# Laser_Teensy_proto_edits_11-21.net
KiCad netlist of a schematic drawn in EAGLE
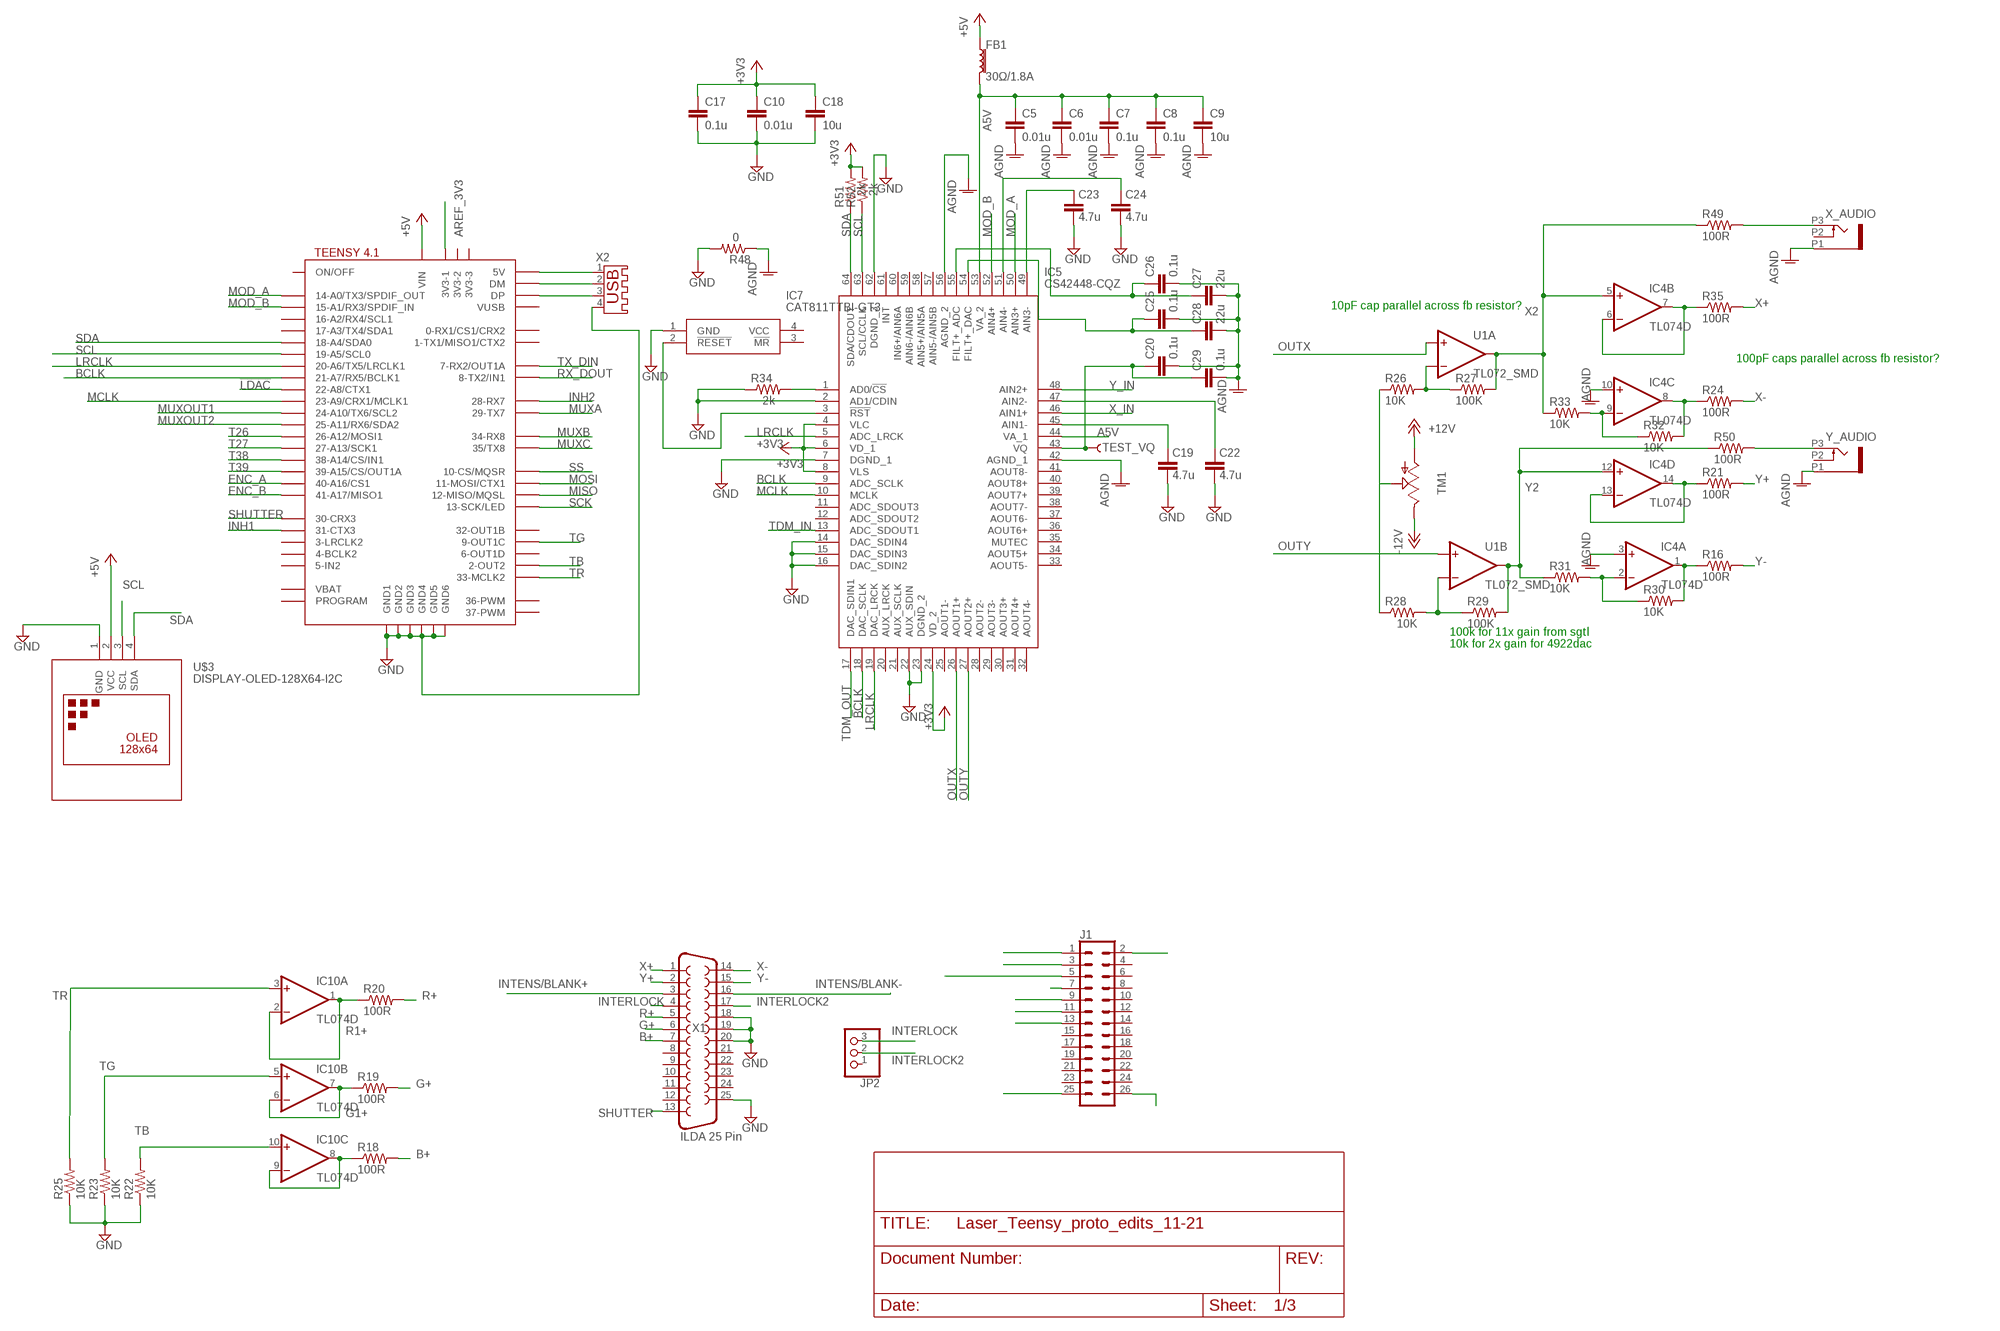
[diagram p0: schematic, sheet 1]
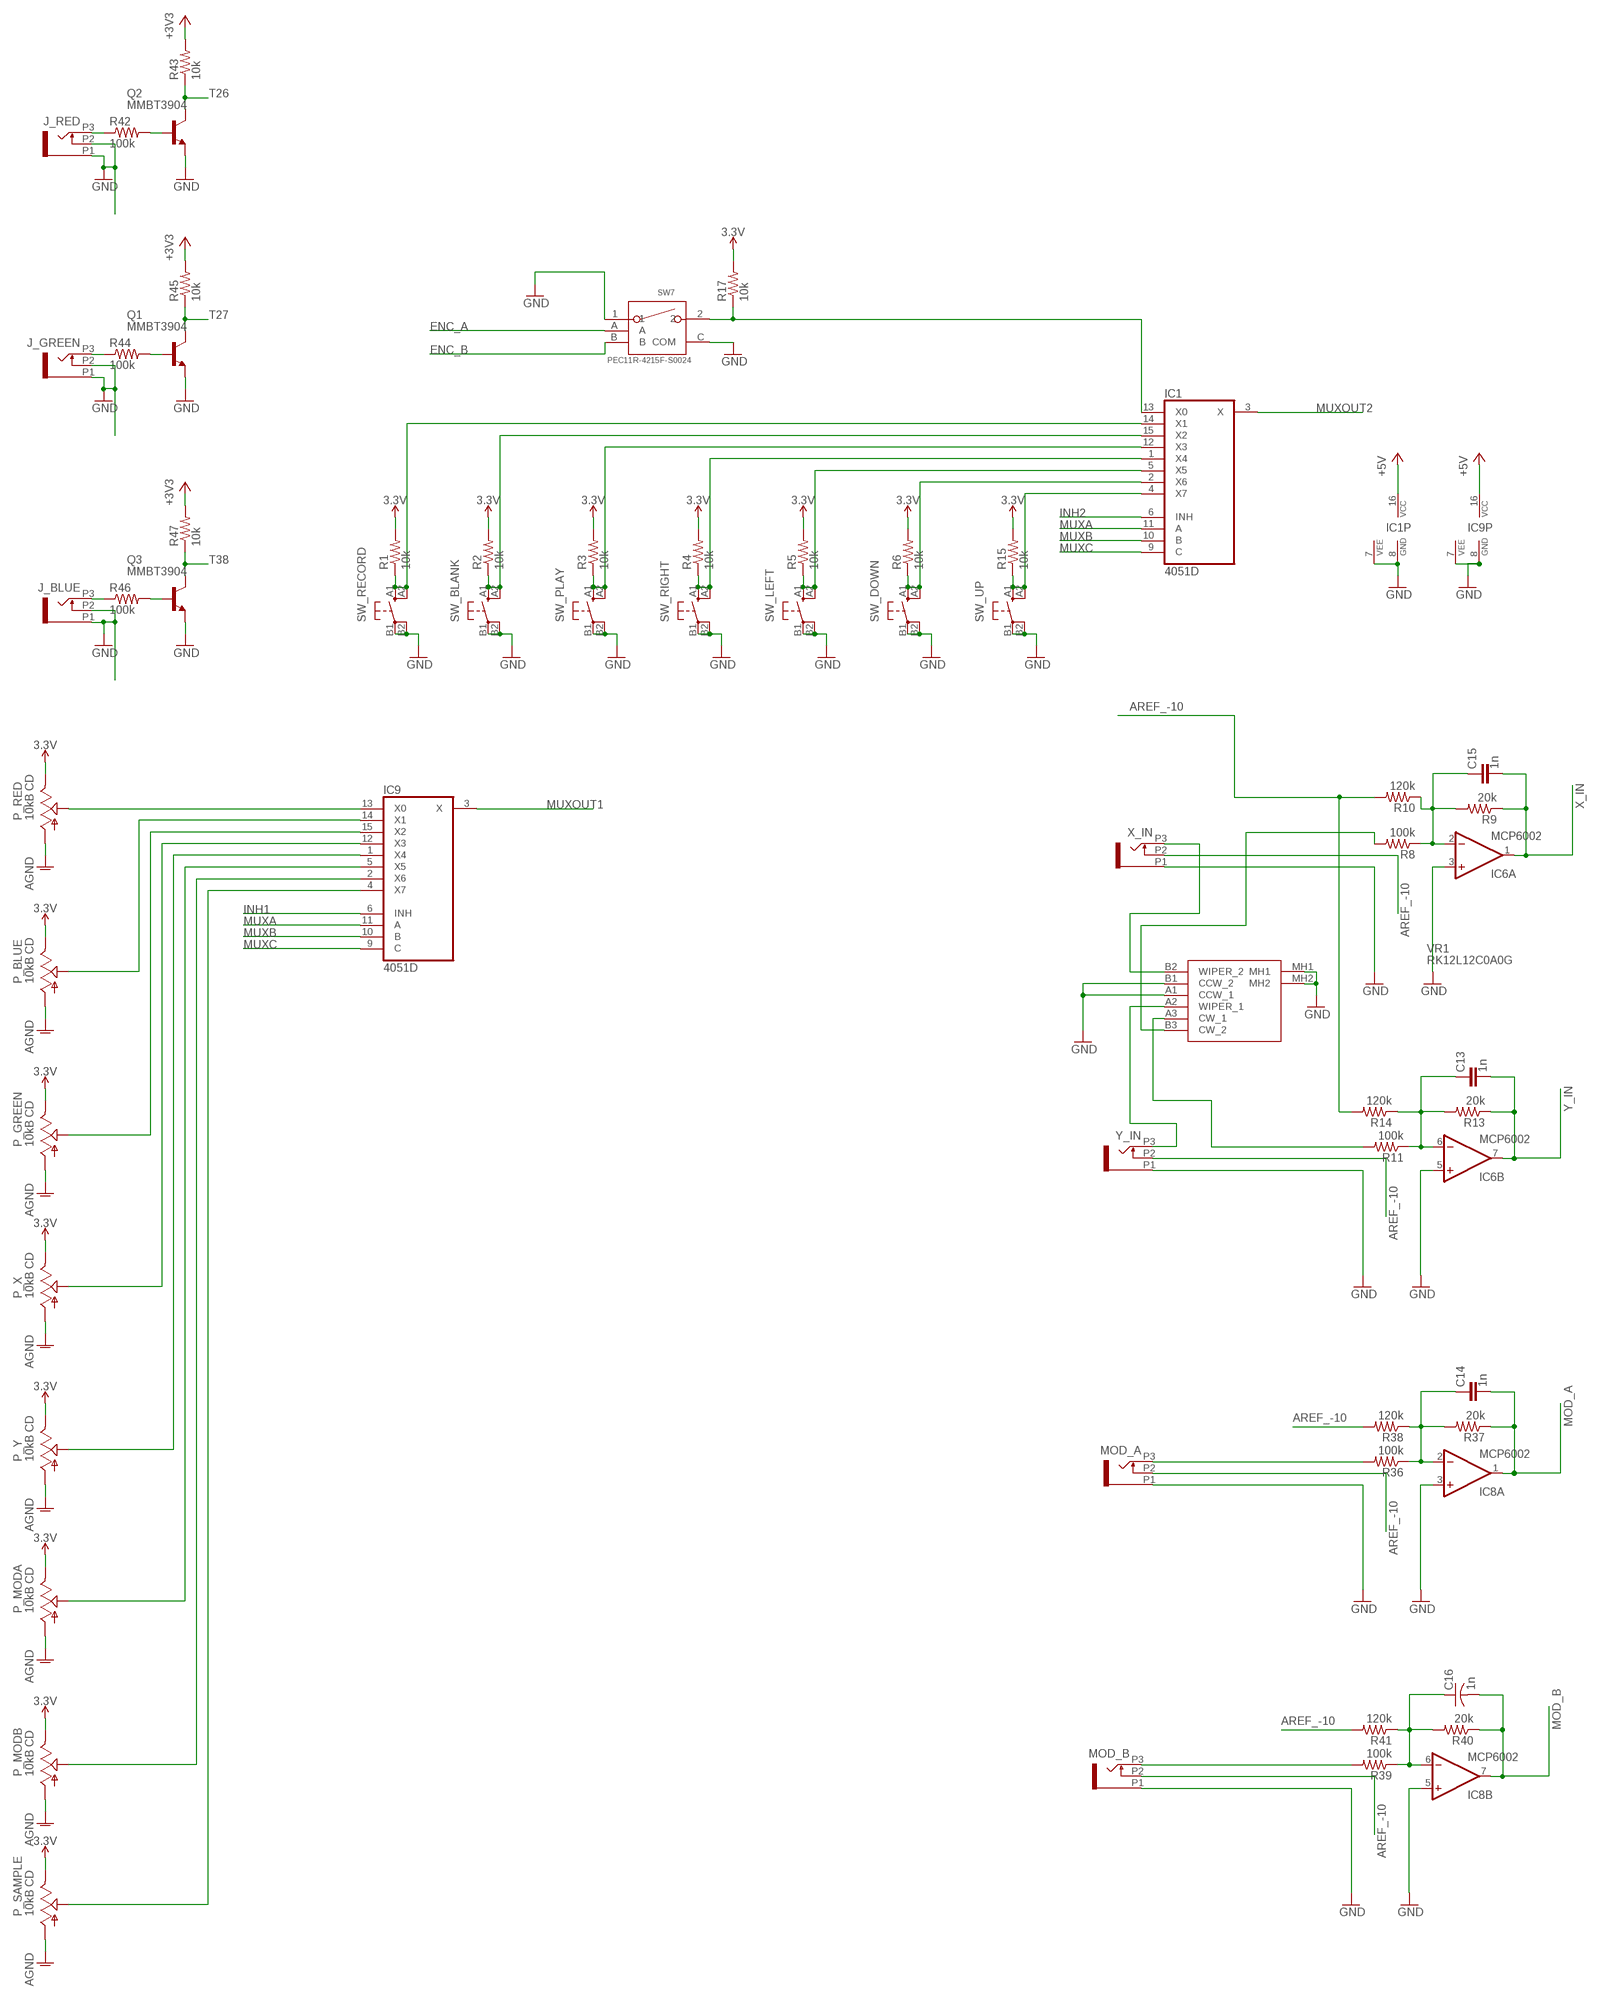
[diagram p1: schematic, sheet 2]
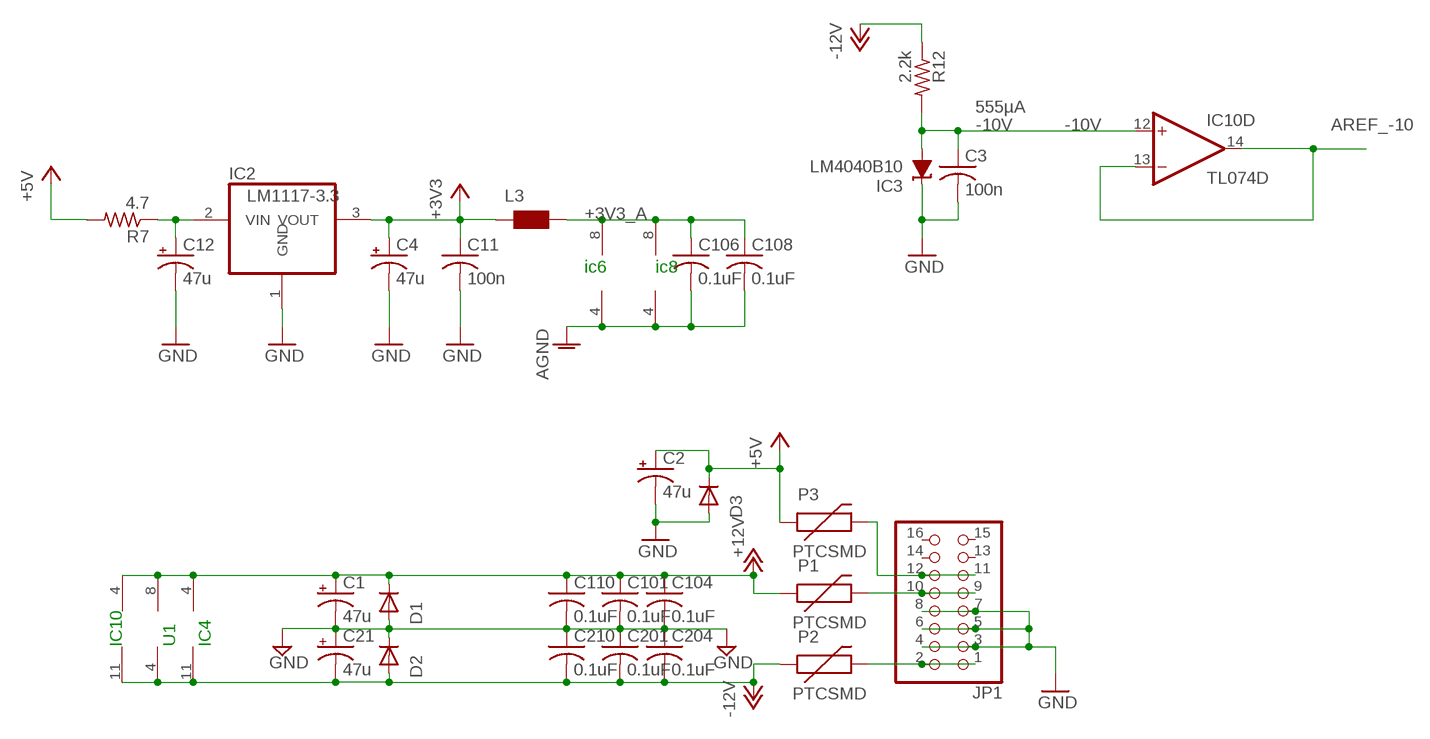
[diagram p2: schematic, sheet 3]

(export (version "E")
  (design (tool "Eeschema 10.0.6"))
  (components
    (comp (ref "C13")
      (value "1n")
      (footprint "eagle-import:C0603")
      (libsource (lib "eagle-import") (part "C-EUC0603"))
    )
    (comp (ref "C14")
      (value "1n")
      (footprint "eagle-import:C0603")
      (libsource (lib "eagle-import") (part "C-EUC0603"))
    )
    (comp (ref "C15")
      (value "1n")
      (footprint "eagle-import:C0603")
      (libsource (lib "eagle-import") (part "C-EUC0603"))
    )
    (comp (ref "C16")
      (value "1n")
      (footprint "eagle-import:C0603K")
      (libsource (lib "eagle-import") (part "rcl_334_C-USC0603K"))
    )
    (comp (ref "IC1")
      (value "4051D")
      (footprint "eagle-import:SO16")
      (libsource (lib "eagle-import") (part "4051D"))
    )
    (comp (ref "IC6")
      (value "MCP6002")
      (footprint "eagle-import:SO08")
      (libsource (lib "eagle-import") (part "TL072D"))
    )
    (comp (ref "IC8")
      (value "MCP6002")
      (footprint "eagle-import:SO08")
      (libsource (lib "eagle-import") (part "TL072D"))
    )
    (comp (ref "IC9")
      (value "4051D")
      (footprint "eagle-import:SO16")
      (libsource (lib "eagle-import") (part "4051D"))
    )
    (comp (ref "J_BLUE")
      (value "PJ301_THONKICONN6")
      (footprint "eagle-import:WQP_PJ_301M6")
      (libsource (lib "eagle-import") (part "PJ301_THONKICONN6"))
    )
    (comp (ref "J_GREEN")
      (value "PJ301_THONKICONN6")
      (footprint "eagle-import:WQP_PJ_301M6")
      (libsource (lib "eagle-import") (part "PJ301_THONKICONN6"))
    )
    (comp (ref "J_RED")
      (value "PJ301_THONKICONN6")
      (footprint "eagle-import:WQP_PJ_301M6")
      (libsource (lib "eagle-import") (part "PJ301_THONKICONN6"))
    )
    (comp (ref "MOD_A")
      (value "PJ301_THONKICONN6")
      (footprint "eagle-import:WQP_PJ_301M6")
      (libsource (lib "eagle-import") (part "og-pj301_variations_PJ301_THONKICONN6"))
    )
    (comp (ref "MOD_B")
      (value "PJ301_THONKICONN6")
      (footprint "eagle-import:WQP_PJ_301M6")
      (libsource (lib "eagle-import") (part "og-pj301_variations_PJ301_THONKICONN6"))
    )
    (comp (ref "P_BLUE")
      (value "10kB CD")
      (footprint "eagle-import:ALPS_POT_VERTICAL_PS")
      (libsource (lib "eagle-import") (part "POT_USVERTICAL_PS"))
    )
    (comp (ref "P_GREEN")
      (value "10kB CD")
      (footprint "eagle-import:ALPS_POT_VERTICAL_PS")
      (libsource (lib "eagle-import") (part "POT_USVERTICAL_PS"))
    )
    (comp (ref "P_MODA")
      (value "10kB CD")
      (footprint "eagle-import:ALPS_POT_VERTICAL_PS")
      (libsource (lib "eagle-import") (part "POT_USVERTICAL_PS"))
    )
    (comp (ref "P_MODB")
      (value "10kB CD")
      (footprint "eagle-import:ALPS_POT_VERTICAL_PS")
      (libsource (lib "eagle-import") (part "POT_USVERTICAL_PS"))
    )
    (comp (ref "P_RED")
      (value "10kB CD")
      (footprint "eagle-import:ALPS_POT_VERTICAL_PS")
      (libsource (lib "eagle-import") (part "POT_USVERTICAL_PS"))
    )
    (comp (ref "P_SAMPLE")
      (value "10kB CD")
      (footprint "eagle-import:ALPS_POT_VERTICAL_PS")
      (libsource (lib "eagle-import") (part "POT_USVERTICAL_PS"))
    )
    (comp (ref "P_X")
      (value "10kB CD")
      (footprint "eagle-import:ALPS_POT_VERTICAL_PS")
      (libsource (lib "eagle-import") (part "POT_USVERTICAL_PS"))
    )
    (comp (ref "P_Y")
      (value "10kB CD")
      (footprint "eagle-import:ALPS_POT_VERTICAL_PS")
      (libsource (lib "eagle-import") (part "POT_USVERTICAL_PS"))
    )
    (comp (ref "Q1")
      (value "MMBT3904")
      (footprint "eagle-import:SOT23-BEC")
      (libsource (lib "eagle-import") (part "-NPN-SOT23-BECMMBT3904LT1"))
    )
    (comp (ref "Q2")
      (value "MMBT3904")
      (footprint "eagle-import:SOT23-BEC")
      (libsource (lib "eagle-import") (part "-NPN-SOT23-BECMMBT3904LT1"))
    )
    (comp (ref "Q3")
      (value "MMBT3904")
      (footprint "eagle-import:SOT23-BEC")
      (libsource (lib "eagle-import") (part "-NPN-SOT23-BECMMBT3904LT1"))
    )
    (comp (ref "R1")
      (value "10k")
      (footprint "eagle-import:R0603")
      (libsource (lib "eagle-import") (part "rcl_334_R-US_R0603"))
    )
    (comp (ref "R2")
      (value "10k")
      (footprint "eagle-import:R0603")
      (libsource (lib "eagle-import") (part "rcl_334_R-US_R0603"))
    )
    (comp (ref "R3")
      (value "10k")
      (footprint "eagle-import:R0603")
      (libsource (lib "eagle-import") (part "rcl_334_R-US_R0603"))
    )
    (comp (ref "R4")
      (value "10k")
      (footprint "eagle-import:R0603")
      (libsource (lib "eagle-import") (part "rcl_334_R-US_R0603"))
    )
    (comp (ref "R5")
      (value "10k")
      (footprint "eagle-import:R0603")
      (libsource (lib "eagle-import") (part "rcl_334_R-US_R0603"))
    )
    (comp (ref "R6")
      (value "10k")
      (footprint "eagle-import:R0603")
      (libsource (lib "eagle-import") (part "rcl_334_R-US_R0603"))
    )
    (comp (ref "R8")
      (value "100k")
      (footprint "eagle-import:R0603")
      (libsource (lib "eagle-import") (part "rcl_334_R-US_R0603"))
    )
    (comp (ref "R9")
      (value "20k")
      (footprint "eagle-import:R0603")
      (libsource (lib "eagle-import") (part "rcl_334_R-US_R0603"))
    )
    (comp (ref "R10")
      (value "120k")
      (footprint "eagle-import:R0603")
      (libsource (lib "eagle-import") (part "rcl_334_R-US_R0603"))
    )
    (comp (ref "R11")
      (value "100k")
      (footprint "eagle-import:R0603")
      (libsource (lib "eagle-import") (part "rcl_334_R-US_R0603"))
    )
    (comp (ref "R13")
      (value "20k")
      (footprint "eagle-import:R0603")
      (libsource (lib "eagle-import") (part "rcl_334_R-US_R0603"))
    )
    (comp (ref "R14")
      (value "120k")
      (footprint "eagle-import:R0603")
      (libsource (lib "eagle-import") (part "rcl_334_R-US_R0603"))
    )
    (comp (ref "R15")
      (value "10k")
      (footprint "eagle-import:R0603")
      (libsource (lib "eagle-import") (part "rcl_334_R-US_R0603"))
    )
    (comp (ref "R17")
      (value "10k")
      (footprint "eagle-import:R0603")
      (libsource (lib "eagle-import") (part "rcl_334_R-US_R0603"))
    )
    (comp (ref "R36")
      (value "100k")
      (footprint "eagle-import:R0603")
      (libsource (lib "eagle-import") (part "rcl_334_R-US_R0603"))
    )
    (comp (ref "R37")
      (value "20k")
      (footprint "eagle-import:R0603")
      (libsource (lib "eagle-import") (part "rcl_334_R-US_R0603"))
    )
    (comp (ref "R38")
      (value "120k")
      (footprint "eagle-import:R0603")
      (libsource (lib "eagle-import") (part "rcl_334_R-US_R0603"))
    )
    (comp (ref "R39")
      (value "100k")
      (footprint "eagle-import:R0603")
      (libsource (lib "eagle-import") (part "rcl_334_R-US_R0603"))
    )
    (comp (ref "R40")
      (value "20k")
      (footprint "eagle-import:R0603")
      (libsource (lib "eagle-import") (part "rcl_334_R-US_R0603"))
    )
    (comp (ref "R41")
      (value "120k")
      (footprint "eagle-import:R0603")
      (libsource (lib "eagle-import") (part "rcl_334_R-US_R0603"))
    )
    (comp (ref "R42")
      (value "100k")
      (footprint "eagle-import:R0603")
      (libsource (lib "eagle-import") (part "rcl_334_R-US_R0603"))
    )
    (comp (ref "R43")
      (value "10k")
      (footprint "eagle-import:R0603")
      (libsource (lib "eagle-import") (part "rcl_334_R-US_R0603"))
    )
    (comp (ref "R44")
      (value "100k")
      (footprint "eagle-import:R0603")
      (libsource (lib "eagle-import") (part "rcl_334_R-US_R0603"))
    )
    (comp (ref "R45")
      (value "10k")
      (footprint "eagle-import:R0603")
      (libsource (lib "eagle-import") (part "rcl_334_R-US_R0603"))
    )
    (comp (ref "R46")
      (value "100k")
      (footprint "eagle-import:R0603")
      (libsource (lib "eagle-import") (part "rcl_334_R-US_R0603"))
    )
    (comp (ref "R47")
      (value "10k")
      (footprint "eagle-import:R0603")
      (libsource (lib "eagle-import") (part "rcl_334_R-US_R0603"))
    )
    (comp (ref "SW7")
      (value "PEC11R-4215F-S0024")
      (footprint "eagle-import:PEC11R-4215F-S0024")
      (fields
        (field (name "DIGIKEY_PART_NUMBER") "PEC11R-4215F-S0024-ND")
        (field (name "MANUFACTURER") "Bourns Inc.")
        (field (name "CREATED_BY") "PCBLayout.com")
      )
      (libsource (lib "eagle-import") (part "PEC11R-4215F-S0024"))
    )
    (comp (ref "SW_BLANK")
      (value "D6R")
      (footprint "eagle-import:D6R")
      (libsource (lib "eagle-import") (part "D6R"))
    )
    (comp (ref "SW_DOWN")
      (value "D6R")
      (footprint "eagle-import:D6R")
      (libsource (lib "eagle-import") (part "D6R"))
    )
    (comp (ref "SW_LEFT")
      (value "D6R")
      (footprint "eagle-import:D6R")
      (libsource (lib "eagle-import") (part "D6R"))
    )
    (comp (ref "SW_PLAY")
      (value "D6R")
      (footprint "eagle-import:D6R")
      (libsource (lib "eagle-import") (part "D6R"))
    )
    (comp (ref "SW_RECORD")
      (value "D6R")
      (footprint "eagle-import:D6R")
      (libsource (lib "eagle-import") (part "D6R"))
    )
    (comp (ref "SW_RIGHT")
      (value "D6R")
      (footprint "eagle-import:D6R")
      (libsource (lib "eagle-import") (part "D6R"))
    )
    (comp (ref "SW_UP")
      (value "D6R")
      (footprint "eagle-import:D6R")
      (libsource (lib "eagle-import") (part "D6R"))
    )
    (comp (ref "VR1")
      (value "RK12L12C0A0G")
      (footprint "eagle-import:RK12L12C0A0G")
      (fields (field (name "MOUSER_PART_NUMBER") "688-RK12L12C0A0G"))
      (libsource (lib "eagle-import") (part "RK12L12C0A0G"))
    )
    (comp (ref "X_IN")
      (value "PJ301_THONKICONN6")
      (footprint "eagle-import:WQP_PJ_301M6")
      (libsource (lib "eagle-import") (part "og-pj301_variations_PJ301_THONKICONN6"))
    )
    (comp (ref "Y_IN")
      (value "PJ301_THONKICONN6")
      (footprint "eagle-import:WQP_PJ_301M6")
      (libsource (lib "eagle-import") (part "og-pj301_variations_PJ301_THONKICONN6"))
    )
    (comp (ref "C5")
      (value "0.01u")
      (footprint "eagle-import:C0603")
      (libsource (lib "eagle-import") (part "C-EUC0603"))
    )
    (comp (ref "C6")
      (value "0.01u")
      (footprint "eagle-import:C0603")
      (libsource (lib "eagle-import") (part "C-EUC0603"))
    )
    (comp (ref "C7")
      (value "0.1u")
      (footprint "eagle-import:C0603")
      (libsource (lib "eagle-import") (part "C-EUC0603"))
    )
    (comp (ref "C8")
      (value "0.1u")
      (footprint "eagle-import:C0603")
      (libsource (lib "eagle-import") (part "C-EUC0603"))
    )
    (comp (ref "C9")
      (value "10u")
      (footprint "eagle-import:C0603")
      (libsource (lib "eagle-import") (part "C-EUC0603"))
    )
    (comp (ref "C10")
      (value "0.01u")
      (footprint "eagle-import:C0603")
      (libsource (lib "eagle-import") (part "C-EUC0603"))
    )
    (comp (ref "C17")
      (value "0.1u")
      (footprint "eagle-import:C0603")
      (libsource (lib "eagle-import") (part "C-EUC0603"))
    )
    (comp (ref "C18")
      (value "10u")
      (footprint "eagle-import:C0603")
      (libsource (lib "eagle-import") (part "C-EUC0603"))
    )
    (comp (ref "C19")
      (value "4.7u")
      (footprint "eagle-import:C0603")
      (libsource (lib "eagle-import") (part "C-EUC0603"))
    )
    (comp (ref "C20")
      (value "0.1u")
      (footprint "eagle-import:C0603")
      (libsource (lib "eagle-import") (part "C-EUC0603"))
    )
    (comp (ref "C22")
      (value "4.7u")
      (footprint "eagle-import:C0603")
      (libsource (lib "eagle-import") (part "C-EUC0603"))
    )
    (comp (ref "C23")
      (value "4.7u")
      (footprint "eagle-import:C0603")
      (libsource (lib "eagle-import") (part "C-EUC0603"))
    )
    (comp (ref "C24")
      (value "4.7u")
      (footprint "eagle-import:C0603")
      (libsource (lib "eagle-import") (part "C-EUC0603"))
    )
    (comp (ref "C25")
      (value "0.1u")
      (footprint "eagle-import:C0603")
      (libsource (lib "eagle-import") (part "C-EUC0603"))
    )
    (comp (ref "C26")
      (value "0.1u")
      (footprint "eagle-import:C0603")
      (libsource (lib "eagle-import") (part "C-EUC0603"))
    )
    (comp (ref "C27")
      (value "22u")
      (footprint "eagle-import:C0603")
      (libsource (lib "eagle-import") (part "C-EUC0603"))
    )
    (comp (ref "C28")
      (value "22u")
      (footprint "eagle-import:C0603")
      (libsource (lib "eagle-import") (part "C-EUC0603"))
    )
    (comp (ref "C29")
      (value "0.1u")
      (footprint "eagle-import:C0603")
      (libsource (lib "eagle-import") (part "C-EUC0603"))
    )
    (comp (ref "FB1")
      (value "30Ω/1.8A")
      (footprint "eagle-import:0603")
      (libsource (lib "eagle-import") (part "FERRITE_BEAD-0603"))
    )
    (comp (ref "IC4")
      (value "TL074D")
      (footprint "eagle-import:SO14")
      (libsource (lib "eagle-import") (part "TL074D"))
    )
    (comp (ref "IC5")
      (value "CS42448-CQZ")
      (footprint "eagle-import:QFP50P1200X1200X160-64N")
      (fields (field (name "MOUSER_PART_NUMBER") "777-CS42448-CQZ"))
      (libsource (lib "eagle-import") (part "CS42448-CQZ"))
    )
    (comp (ref "IC7")
      (value "CAT811TTBI-GT3")
      (footprint "eagle-import:4-PIN-SOT-143(BI-SUFFIX-CASE-5")
      (fields (field (name "MOUSER_PART_NUMBER") "698-CAT811TTBI-GT3"))
      (libsource (lib "eagle-import") (part "CAT811TTBI-GT3"))
    )
    (comp (ref "IC10")
      (value "TL074D")
      (footprint "eagle-import:SO14")
      (libsource (lib "eagle-import") (part "TL074D"))
    )
    (comp (ref "J1")
      (value "CONN_13X22X13")
      (footprint "eagle-import:2X13")
      (libsource (lib "eagle-import") (part "CONN_13X22X13"))
    )
    (comp (ref "JP2")
      (value "PINHD-1X3")
      (footprint "eagle-import:1X03")
      (libsource (lib "eagle-import") (part "PINHD-1X3"))
    )
    (comp (ref "R16")
      (value "100R")
      (footprint "eagle-import:R0603")
      (libsource (lib "eagle-import") (part "rcl_334_R-US_R0603"))
    )
    (comp (ref "R18")
      (value "100R")
      (footprint "eagle-import:R0603")
      (libsource (lib "eagle-import") (part "rcl_334_R-US_R0603"))
    )
    (comp (ref "R19")
      (value "100R")
      (footprint "eagle-import:R0603")
      (libsource (lib "eagle-import") (part "rcl_334_R-US_R0603"))
    )
    (comp (ref "R20")
      (value "100R")
      (footprint "eagle-import:R0603")
      (libsource (lib "eagle-import") (part "rcl_334_R-US_R0603"))
    )
    (comp (ref "R21")
      (value "100R")
      (footprint "eagle-import:R0603")
      (libsource (lib "eagle-import") (part "rcl_334_R-US_R0603"))
    )
    (comp (ref "R22")
      (value "10K")
      (footprint "eagle-import:R0603")
      (libsource (lib "eagle-import") (part "rcl_334_R-US_R0603"))
    )
    (comp (ref "R23")
      (value "10K")
      (footprint "eagle-import:R0603")
      (libsource (lib "eagle-import") (part "rcl_334_R-US_R0603"))
    )
    (comp (ref "R24")
      (value "100R")
      (footprint "eagle-import:R0603")
      (libsource (lib "eagle-import") (part "rcl_334_R-US_R0603"))
    )
    (comp (ref "R25")
      (value "10K")
      (footprint "eagle-import:R0603")
      (libsource (lib "eagle-import") (part "rcl_334_R-US_R0603"))
    )
    (comp (ref "R26")
      (value "10K")
      (footprint "eagle-import:R0603")
      (libsource (lib "eagle-import") (part "rcl_334_R-US_R0603"))
    )
    (comp (ref "R27")
      (value "100K")
      (footprint "eagle-import:R0603")
      (libsource (lib "eagle-import") (part "rcl_334_R-US_R0603"))
    )
    (comp (ref "R28")
      (value "10K")
      (footprint "eagle-import:R0603")
      (libsource (lib "eagle-import") (part "rcl_334_R-US_R0603"))
    )
    (comp (ref "R29")
      (value "100K")
      (footprint "eagle-import:R0603")
      (libsource (lib "eagle-import") (part "rcl_334_R-US_R0603"))
    )
    (comp (ref "R30")
      (value "10K")
      (footprint "eagle-import:R0603")
      (libsource (lib "eagle-import") (part "rcl_334_R-US_R0603"))
    )
    (comp (ref "R31")
      (value "10K")
      (footprint "eagle-import:R0603")
      (libsource (lib "eagle-import") (part "rcl_334_R-US_R0603"))
    )
    (comp (ref "R32")
      (value "10K")
      (footprint "eagle-import:R0603")
      (libsource (lib "eagle-import") (part "resistor_R-US_R0603"))
    )
    (comp (ref "R33")
      (value "10K")
      (footprint "eagle-import:R0603")
      (libsource (lib "eagle-import") (part "rcl_334_R-US_R0603"))
    )
    (comp (ref "R34")
      (value "2k")
      (footprint "eagle-import:R0603")
      (libsource (lib "eagle-import") (part "rcl_334_R-US_R0603"))
    )
    (comp (ref "R35")
      (value "100R")
      (footprint "eagle-import:R0603")
      (libsource (lib "eagle-import") (part "rcl_334_R-US_R0603"))
    )
    (comp (ref "R48")
      (value "0")
      (footprint "eagle-import:R0603")
      (libsource (lib "eagle-import") (part "rcl_334_R-US_R0603"))
    )
    (comp (ref "R49")
      (value "100R")
      (footprint "eagle-import:R0603")
      (libsource (lib "eagle-import") (part "rcl_334_R-US_R0603"))
    )
    (comp (ref "R50")
      (value "100R")
      (footprint "eagle-import:R0603")
      (libsource (lib "eagle-import") (part "rcl_334_R-US_R0603"))
    )
    (comp (ref "R51")
      (value "2k")
      (footprint "eagle-import:R0603")
      (libsource (lib "eagle-import") (part "rcl_334_R-US_R0603"))
    )
    (comp (ref "R52")
      (value "2k")
      (footprint "eagle-import:R0603")
      (libsource (lib "eagle-import") (part "rcl_334_R-US_R0603"))
    )
    (comp (ref "TEST_VQ")
      (value "TEST-VQ")
      (footprint "eagle-import:PAD.03X.03")
      (libsource (lib "eagle-import") (part "TEST-POINT3"))
    )
    (comp (ref "TM1")
      (value "TRIM")
      (footprint "eagle-import:6MM")
      (libsource (lib "eagle-import") (part "TRIM"))
    )
    (comp (ref "U$2")
      (value "TEENSY41-E")
      (footprint "eagle-import:TENNSY41-E")
      (libsource (lib "eagle-import") (part "TEENSY41-E"))
    )
    (comp (ref "U$3")
      (value "DISPLAY-OLED-128X64-I2C")
      (footprint "eagle-import:DISPLAY-OLED-128X64-I2C")
      (libsource (lib "eagle-import") (part "DISPLAY-OLED-128X64-I2C"))
    )
    (comp (ref "U1")
      (value "TL072_SMD")
      (footprint "eagle-import:SO08")
      (libsource (lib "eagle-import") (part "TL072_SMD"))
    )
    (comp (ref "X1")
      (value "ILDA 25 Pin")
      (footprint "eagle-import:F25D")
      (libsource (lib "eagle-import") (part "F25D"))
    )
    (comp (ref "X2")
      (value "USB-A003")
      (footprint "eagle-import:USB-A003")
      (libsource (lib "eagle-import") (part "USB-A003"))
    )
    (comp (ref "X_AUDIO")
      (value "PJ301_THONKICONN6")
      (footprint "eagle-import:WQP_PJ_301M6")
      (libsource (lib "eagle-import") (part "og-pj301_variations_PJ301_THONKICONN6"))
    )
    (comp (ref "Y_AUDIO")
      (value "PJ301_THONKICONN6")
      (footprint "eagle-import:WQP_PJ_301M6")
      (libsource (lib "eagle-import") (part "og-pj301_variations_PJ301_THONKICONN6"))
    )
    (comp (ref "C1")
      (value "47u")
      (footprint "eagle-import:E3,5-8")
      (libsource (lib "eagle-import") (part "CPOL-USE3.5-8"))
    )
    (comp (ref "C2")
      (value "47u")
      (footprint "eagle-import:E3,5-8")
      (libsource (lib "eagle-import") (part "CPOL-USE3.5-8"))
    )
    (comp (ref "C3")
      (value "100n")
      (footprint "eagle-import:C0603")
      (libsource (lib "eagle-import") (part "rcl_C-USC0603"))
    )
    (comp (ref "C4")
      (value "47u")
      (footprint "eagle-import:E3,5-8")
      (libsource (lib "eagle-import") (part "CPOL-USE3.5-8"))
    )
    (comp (ref "C11")
      (value "100n")
      (footprint "eagle-import:C0603")
      (libsource (lib "eagle-import") (part "rcl_C-USC0603"))
    )
    (comp (ref "C12")
      (value "47u")
      (footprint "eagle-import:E3,5-8")
      (libsource (lib "eagle-import") (part "CPOL-USE3.5-8"))
    )
    (comp (ref "C21")
      (value "47u")
      (footprint "eagle-import:E3,5-8")
      (libsource (lib "eagle-import") (part "CPOL-USE3.5-8"))
    )
    (comp (ref "C101")
      (value "0.1uF")
      (footprint "eagle-import:C0603")
      (libsource (lib "eagle-import") (part "C-USC0603"))
    )
    (comp (ref "C104")
      (value "0.1uF")
      (footprint "eagle-import:C0603")
      (libsource (lib "eagle-import") (part "C-USC0603"))
    )
    (comp (ref "C106")
      (value "0.1uF")
      (footprint "eagle-import:C0603")
      (libsource (lib "eagle-import") (part "C-USC0603"))
    )
    (comp (ref "C108")
      (value "0.1uF")
      (footprint "eagle-import:C0603")
      (libsource (lib "eagle-import") (part "C-USC0603"))
    )
    (comp (ref "C110")
      (value "0.1uF")
      (footprint "eagle-import:C0603")
      (libsource (lib "eagle-import") (part "C-USC0603"))
    )
    (comp (ref "C201")
      (value "0.1uF")
      (footprint "eagle-import:C0603")
      (libsource (lib "eagle-import") (part "C-USC0603"))
    )
    (comp (ref "C204")
      (value "0.1uF")
      (footprint "eagle-import:C0603")
      (libsource (lib "eagle-import") (part "C-USC0603"))
    )
    (comp (ref "C210")
      (value "0.1uF")
      (footprint "eagle-import:C0603")
      (libsource (lib "eagle-import") (part "C-USC0603"))
    )
    (comp (ref "D1")
      (value "1N5819HW")
      (footprint "eagle-import:SOD123")
      (libsource (lib "eagle-import") (part "DIODE-SOD123"))
    )
    (comp (ref "D2")
      (value "1N5819HW")
      (footprint "eagle-import:SOD123")
      (libsource (lib "eagle-import") (part "DIODE-SOD123"))
    )
    (comp (ref "D3")
      (value "1N5819HW")
      (footprint "eagle-import:SOD123")
      (libsource (lib "eagle-import") (part "DIODE-SOD123"))
    )
    (comp (ref "IC2")
      (value "LM1117-3.3")
      (footprint "eagle-import:TO252")
      (libsource (lib "eagle-import") (part "REG1117T"))
    )
    (comp (ref "IC3")
      (value "LM4040B10")
      (footprint "eagle-import:DBZ_R-PDSO-G3")
      (libsource (lib "eagle-import") (part "LM4041DBZB12"))
    )
    (comp (ref "JP1")
      (value "PINHD-2X8")
      (footprint "eagle-import:2X08")
      (libsource (lib "eagle-import") (part "PINHD-2X8"))
    )
    (comp (ref "L3")
      (value "WE-CBF_0603")
      (footprint "eagle-import:0603")
      (libsource (lib "eagle-import") (part "WE-CBF_0603"))
    )
    (comp (ref "P1")
      (value "PTCSMD")
      (footprint "eagle-import:PTC-1206")
      (libsource (lib "eagle-import") (part "PTCSMD"))
    )
    (comp (ref "P2")
      (value "PTCSMD")
      (footprint "eagle-import:PTC-1206")
      (libsource (lib "eagle-import") (part "PTCSMD"))
    )
    (comp (ref "P3")
      (value "PTCSMD")
      (footprint "eagle-import:PTC-1206")
      (libsource (lib "eagle-import") (part "PTCSMD"))
    )
    (comp (ref "R7")
      (value "4.7")
      (footprint "eagle-import:R0603")
      (libsource (lib "eagle-import") (part "R-US_R0603"))
    )
    (comp (ref "R12")
      (value "2.2k")
      (footprint "eagle-import:R0603")
      (libsource (lib "eagle-import") (part "rcl_334_R-US_R0603"))
    )
  )
  (nets
    (net (code "1") (name "+3V3") (class "Default")
      (node (ref "C10") (pin "1") (pinfunction "1_1") (pintype "passive"))
      (node (ref "C11") (pin "1") (pinfunction "1_1") (pintype "passive"))
      (node (ref "C17") (pin "1") (pinfunction "1_1") (pintype "passive"))
      (node (ref "C18") (pin "1") (pinfunction "1_1") (pintype "passive"))
      (node (ref "C4") (pin "+") (pinfunction "+_+") (pintype "passive"))
      (node (ref "IC2") (pin "3") (pinfunction "VOUT_3") (pintype "output"))
      (node (ref "IC5") (pin "24") (pinfunction "VD_2_24") (pintype "bidirectional"))
      (node (ref "IC5") (pin "4") (pinfunction "VLC_4") (pintype "bidirectional"))
      (node (ref "IC5") (pin "6") (pinfunction "VD_1_6") (pintype "bidirectional"))
      (node (ref "IC5") (pin "8") (pinfunction "VLS_8") (pintype "bidirectional"))
      (node (ref "L3") (pin "1") (pinfunction "1_1") (pintype "passive"))
      (node (ref "R43") (pin "2") (pinfunction "2_2") (pintype "passive"))
      (node (ref "R45") (pin "2") (pinfunction "2_2") (pintype "passive"))
      (node (ref "R47") (pin "2") (pinfunction "2_2") (pintype "passive"))
      (node (ref "R51") (pin "2") (pinfunction "2_2") (pintype "passive"))
      (node (ref "R52") (pin "2") (pinfunction "2_2") (pintype "passive"))
    )
    (net (code "2") (name "+3V3_A") (class "Default")
      (node (ref "C106") (pin "1") (pinfunction "1_1") (pintype "passive"))
      (node (ref "C108") (pin "1") (pinfunction "1_1") (pintype "passive"))
      (node (ref "IC6") (pin "8") (pinfunction "V+_8") (pintype "power_in"))
      (node (ref "IC8") (pin "8") (pinfunction "V+_8") (pintype "power_in"))
      (node (ref "L3") (pin "2") (pinfunction "2_2") (pintype "passive"))
    )
    (net (code "3") (name "+5V") (class "Default")
      (node (ref "C2") (pin "+") (pinfunction "+_+") (pintype "passive"))
      (node (ref "D3") (pin "C") (pinfunction "C_C") (pintype "passive"))
      (node (ref "FB1") (pin "1") (pinfunction "1_1") (pintype "passive"))
      (node (ref "IC1") (pin "16") (pinfunction "VCC_16") (pintype "power_in"))
      (node (ref "IC9") (pin "16") (pinfunction "VCC_16") (pintype "power_in"))
      (node (ref "P3") (pin "1") (pinfunction "1_1") (pintype "bidirectional"))
      (node (ref "R7") (pin "2") (pinfunction "2_2") (pintype "passive"))
      (node (ref "U$2") (pin "VIN") (pinfunction "VIN_VIN") (pintype "bidirectional"))
      (node (ref "U$3") (pin "2") (pinfunction "VCC_2") (pintype "power_in"))
    )
    (net (code "4") (name "+12V") (class "Default")
      (node (ref "C1") (pin "+") (pinfunction "+_+") (pintype "passive"))
      (node (ref "C101") (pin "1") (pinfunction "1_1") (pintype "passive"))
      (node (ref "C104") (pin "1") (pinfunction "1_1") (pintype "passive"))
      (node (ref "C110") (pin "1") (pinfunction "1_1") (pintype "passive"))
      (node (ref "D1") (pin "C") (pinfunction "C_C") (pintype "passive"))
      (node (ref "IC10") (pin "4") (pinfunction "V+_4") (pintype "power_in"))
      (node (ref "IC4") (pin "4") (pinfunction "V+_4") (pintype "power_in"))
      (node (ref "P1") (pin "1") (pinfunction "1_1") (pintype "bidirectional"))
      (node (ref "TM1") (pin "A") (pinfunction "A_A") (pintype "passive"))
      (node (ref "U1") (pin "8") (pinfunction "V+_8") (pintype "power_in"))
    )
    (net (code "5") (name "-10V") (class "Default")
      (node (ref "C3") (pin "1") (pinfunction "1_1") (pintype "passive"))
      (node (ref "IC10") (pin "12") (pinfunction "+IN_12") (pintype "input"))
      (node (ref "IC3") (pin "2") (pinfunction "A_2") (pintype "passive"))
      (node (ref "R12") (pin "2") (pinfunction "2_2") (pintype "passive"))
    )
    (net (code "6") (name "-12V") (class "Default")
      (node (ref "C201") (pin "2") (pinfunction "2_2") (pintype "passive"))
      (node (ref "C204") (pin "2") (pinfunction "2_2") (pintype "passive"))
      (node (ref "C21") (pin "-") (pinfunction "-_-") (pintype "passive"))
      (node (ref "C210") (pin "2") (pinfunction "2_2") (pintype "passive"))
      (node (ref "D2") (pin "A") (pinfunction "A_A") (pintype "passive"))
      (node (ref "IC10") (pin "11") (pinfunction "V-_11") (pintype "power_in"))
      (node (ref "IC4") (pin "11") (pinfunction "V-_11") (pintype "power_in"))
      (node (ref "P2") (pin "1") (pinfunction "1_1") (pintype "bidirectional"))
      (node (ref "R12") (pin "1") (pinfunction "1_1") (pintype "passive"))
      (node (ref "TM1") (pin "E") (pinfunction "E_E") (pintype "passive"))
      (node (ref "U1") (pin "4") (pinfunction "V-_4") (pintype "power_in"))
    )
    (net (code "7") (name "3.3V") (class "Default")
      (node (ref "P_BLUE") (pin "P$1") (pinfunction "E_P$1") (pintype "passive"))
      (node (ref "P_GREEN") (pin "P$1") (pinfunction "E_P$1") (pintype "passive"))
      (node (ref "P_MODA") (pin "P$1") (pinfunction "E_P$1") (pintype "passive"))
      (node (ref "P_MODB") (pin "P$1") (pinfunction "E_P$1") (pintype "passive"))
      (node (ref "P_RED") (pin "P$1") (pinfunction "E_P$1") (pintype "passive"))
      (node (ref "P_SAMPLE") (pin "P$1") (pinfunction "E_P$1") (pintype "passive"))
      (node (ref "P_X") (pin "P$1") (pinfunction "E_P$1") (pintype "passive"))
      (node (ref "P_Y") (pin "P$1") (pinfunction "E_P$1") (pintype "passive"))
      (node (ref "R1") (pin "2") (pinfunction "2_2") (pintype "passive"))
      (node (ref "R15") (pin "2") (pinfunction "2_2") (pintype "passive"))
      (node (ref "R17") (pin "2") (pinfunction "2_2") (pintype "passive"))
      (node (ref "R2") (pin "2") (pinfunction "2_2") (pintype "passive"))
      (node (ref "R3") (pin "2") (pinfunction "2_2") (pintype "passive"))
      (node (ref "R4") (pin "2") (pinfunction "2_2") (pintype "passive"))
      (node (ref "R5") (pin "2") (pinfunction "2_2") (pintype "passive"))
      (node (ref "R6") (pin "2") (pinfunction "2_2") (pintype "passive"))
    )
    (net (code "8") (name "A5V") (class "Default")
      (node (ref "C5") (pin "1") (pinfunction "1_1") (pintype "passive"))
      (node (ref "C6") (pin "1") (pinfunction "1_1") (pintype "passive"))
      (node (ref "C7") (pin "1") (pinfunction "1_1") (pintype "passive"))
      (node (ref "C8") (pin "1") (pinfunction "1_1") (pintype "passive"))
      (node (ref "C9") (pin "1") (pinfunction "1_1") (pintype "passive"))
      (node (ref "FB1") (pin "2") (pinfunction "2_2") (pintype "passive"))
      (node (ref "IC5") (pin "44") (pinfunction "VA_1_44") (pintype "bidirectional"))
      (node (ref "IC5") (pin "53") (pinfunction "VA_2_53") (pintype "bidirectional"))
    )
    (net (code "9") (name "AGND") (class "Default")
      (node (ref "C106") (pin "2") (pinfunction "2_2") (pintype "passive"))
      (node (ref "C108") (pin "2") (pinfunction "2_2") (pintype "passive"))
      (node (ref "C20") (pin "2") (pinfunction "2_2") (pintype "passive"))
      (node (ref "C25") (pin "2") (pinfunction "2_2") (pintype "passive"))
      (node (ref "C26") (pin "2") (pinfunction "2_2") (pintype "passive"))
      (node (ref "C27") (pin "2") (pinfunction "2_2") (pintype "passive"))
      (node (ref "C28") (pin "2") (pinfunction "2_2") (pintype "passive"))
      (node (ref "C29") (pin "2") (pinfunction "2_2") (pintype "passive"))
      (node (ref "C5") (pin "2") (pinfunction "2_2") (pintype "passive"))
      (node (ref "C6") (pin "2") (pinfunction "2_2") (pintype "passive"))
      (node (ref "C7") (pin "2") (pinfunction "2_2") (pintype "passive"))
      (node (ref "C8") (pin "2") (pinfunction "2_2") (pintype "passive"))
      (node (ref "C9") (pin "2") (pinfunction "2_2") (pintype "passive"))
      (node (ref "IC4") (pin "10") (pinfunction "+IN_10") (pintype "input"))
      (node (ref "IC4") (pin "3") (pinfunction "+IN_3") (pintype "input"))
      (node (ref "IC5") (pin "42") (pinfunction "AGND_1_42") (pintype "bidirectional"))
      (node (ref "IC5") (pin "56") (pinfunction "AGND_2_56") (pintype "bidirectional"))
      (node (ref "IC6") (pin "4") (pinfunction "V-_4") (pintype "power_in"))
      (node (ref "IC8") (pin "4") (pinfunction "V-_4") (pintype "power_in"))
      (node (ref "P_BLUE") (pin "P$3") (pinfunction "A_P$3") (pintype "passive"))
      (node (ref "P_GREEN") (pin "P$3") (pinfunction "A_P$3") (pintype "passive"))
      (node (ref "P_MODA") (pin "P$3") (pinfunction "A_P$3") (pintype "passive"))
      (node (ref "P_MODB") (pin "P$3") (pinfunction "A_P$3") (pintype "passive"))
      (node (ref "P_RED") (pin "P$3") (pinfunction "A_P$3") (pintype "passive"))
      (node (ref "P_SAMPLE") (pin "P$3") (pinfunction "A_P$3") (pintype "passive"))
      (node (ref "P_X") (pin "P$3") (pinfunction "A_P$3") (pintype "passive"))
      (node (ref "P_Y") (pin "P$3") (pinfunction "A_P$3") (pintype "passive"))
      (node (ref "R48") (pin "1") (pinfunction "1_1") (pintype "passive"))
      (node (ref "X_AUDIO") (pin "P1") (pinfunction "1_P1") (pintype "passive"))
      (node (ref "Y_AUDIO") (pin "P1") (pinfunction "1_P1") (pintype "passive"))
    )
    (net (code "10") (name "AREF_-10") (class "Default")
      (node (ref "IC10") (pin "13") (pinfunction "-IN_13") (pintype "input"))
      (node (ref "IC10") (pin "14") (pinfunction "OUT_14") (pintype "output"))
      (node (ref "MOD_A") (pin "P2") (pinfunction "2_P2") (pintype "passive"))
      (node (ref "MOD_B") (pin "P2") (pinfunction "2_P2") (pintype "passive"))
      (node (ref "R10") (pin "2") (pinfunction "2_2") (pintype "passive"))
      (node (ref "R14") (pin "2") (pinfunction "2_2") (pintype "passive"))
      (node (ref "R38") (pin "2") (pinfunction "2_2") (pintype "passive"))
      (node (ref "R41") (pin "2") (pinfunction "2_2") (pintype "passive"))
      (node (ref "X_IN") (pin "P2") (pinfunction "2_P2") (pintype "passive"))
      (node (ref "Y_IN") (pin "P2") (pinfunction "2_P2") (pintype "passive"))
    )
    (net (code "11") (name "AREF_3V3") (class "Default")
      (node (ref "U$2") (pin "3V3-1") (pinfunction "3V3-1_3V3-1") (pintype "bidirectional"))
    )
    (net (code "12") (name "B+") (class "Default")
      (node (ref "R18") (pin "2") (pinfunction "2_2") (pintype "passive"))
      (node (ref "X1") (pin "7") (pinfunction "7_7") (pintype "passive"))
    )
    (net (code "13") (name "BCLK") (class "Default")
      (node (ref "IC5") (pin "18") (pinfunction "DAC_SCLK_18") (pintype "bidirectional"))
      (node (ref "IC5") (pin "9") (pinfunction "ADC_SCLK_9") (pintype "bidirectional"))
      (node (ref "U$2") (pin "21-A7/RX5/BCLK1") (pinfunction "21-A7/RX5/BCLK1_21-A7/RX5/BCLK1") (pintype "bidirectional"))
    )
    (net (code "14") (name "ENC_A") (class "Default")
      (node (ref "SW7") (pin "A") (pinfunction "A_A") (pintype "passive"))
      (node (ref "U$2") (pin "40-A16/CS1") (pinfunction "40-A16/CS1_40-A16/CS1") (pintype "bidirectional"))
    )
    (net (code "15") (name "ENC_B") (class "Default")
      (node (ref "SW7") (pin "B") (pinfunction "B_B") (pintype "passive"))
      (node (ref "U$2") (pin "41-A17/MISO1") (pinfunction "41-A17/MISO1_41-A17/MISO1") (pintype "bidirectional"))
    )
    (net (code "16") (name "G+") (class "Default")
      (node (ref "R19") (pin "2") (pinfunction "2_2") (pintype "passive"))
      (node (ref "X1") (pin "6") (pinfunction "6_6") (pintype "passive"))
    )
    (net (code "17") (name "G1+") (class "Default")
      (node (ref "IC10") (pin "6") (pinfunction "-IN_6") (pintype "input"))
      (node (ref "IC10") (pin "7") (pinfunction "OUT_7") (pintype "output"))
      (node (ref "R19") (pin "1") (pinfunction "1_1") (pintype "passive"))
    )
    (net (code "18") (name "GND") (class "Default")
      (node (ref "C1") (pin "-") (pinfunction "-_-") (pintype "passive"))
      (node (ref "C10") (pin "2") (pinfunction "2_2") (pintype "passive"))
      (node (ref "C101") (pin "2") (pinfunction "2_2") (pintype "passive"))
      (node (ref "C104") (pin "2") (pinfunction "2_2") (pintype "passive"))
      (node (ref "C11") (pin "2") (pinfunction "2_2") (pintype "passive"))
      (node (ref "C110") (pin "2") (pinfunction "2_2") (pintype "passive"))
      (node (ref "C12") (pin "-") (pinfunction "-_-") (pintype "passive"))
      (node (ref "C17") (pin "2") (pinfunction "2_2") (pintype "passive"))
      (node (ref "C18") (pin "2") (pinfunction "2_2") (pintype "passive"))
      (node (ref "C19") (pin "2") (pinfunction "2_2") (pintype "passive"))
      (node (ref "C2") (pin "-") (pinfunction "-_-") (pintype "passive"))
      (node (ref "C201") (pin "1") (pinfunction "1_1") (pintype "passive"))
      (node (ref "C204") (pin "1") (pinfunction "1_1") (pintype "passive"))
      (node (ref "C21") (pin "+") (pinfunction "+_+") (pintype "passive"))
      (node (ref "C210") (pin "1") (pinfunction "1_1") (pintype "passive"))
      (node (ref "C22") (pin "2") (pinfunction "2_2") (pintype "passive"))
      (node (ref "C23") (pin "2") (pinfunction "2_2") (pintype "passive"))
      (node (ref "C24") (pin "2") (pinfunction "2_2") (pintype "passive"))
      (node (ref "C3") (pin "2") (pinfunction "2_2") (pintype "passive"))
      (node (ref "C4") (pin "-") (pinfunction "-_-") (pintype "passive"))
      (node (ref "D1") (pin "A") (pinfunction "A_A") (pintype "passive"))
      (node (ref "D2") (pin "C") (pinfunction "C_C") (pintype "passive"))
      (node (ref "D3") (pin "A") (pinfunction "A_A") (pintype "passive"))
      (node (ref "IC1") (pin "7") (pinfunction "VEE_7") (pintype "power_in"))
      (node (ref "IC1") (pin "8") (pinfunction "GND_8") (pintype "power_in"))
      (node (ref "IC2") (pin "1") (pinfunction "GND_1") (pintype "power_in"))
      (node (ref "IC3") (pin "1") (pinfunction "C_1") (pintype "passive"))
      (node (ref "IC5") (pin "14") (pinfunction "DAC_SDIN4_14") (pintype "bidirectional"))
      (node (ref "IC5") (pin "15") (pinfunction "DAC_SDIN3_15") (pintype "bidirectional"))
      (node (ref "IC5") (pin "16") (pinfunction "DAC_SDIN2_16") (pintype "bidirectional"))
      (node (ref "IC5") (pin "2") (pinfunction "AD1/CDIN_2") (pintype "bidirectional"))
      (node (ref "IC5") (pin "22") (pinfunction "AUX_SDIN_22") (pintype "bidirectional"))
      (node (ref "IC5") (pin "23") (pinfunction "DGND_2_23") (pintype "bidirectional"))
      (node (ref "IC5") (pin "62") (pinfunction "DGND_3_62") (pintype "bidirectional"))
      (node (ref "IC5") (pin "7") (pinfunction "DGND_1_7") (pintype "bidirectional"))
      (node (ref "IC6") (pin "3") (pinfunction "+IN_3") (pintype "input"))
      (node (ref "IC6") (pin "5") (pinfunction "+IN_5") (pintype "input"))
      (node (ref "IC7") (pin "1") (pinfunction "GND_1") (pintype "power_in"))
      (node (ref "IC8") (pin "3") (pinfunction "+IN_3") (pintype "input"))
      (node (ref "IC8") (pin "5") (pinfunction "+IN_5") (pintype "input"))
      (node (ref "IC9") (pin "7") (pinfunction "VEE_7") (pintype "power_in"))
      (node (ref "IC9") (pin "8") (pinfunction "GND_8") (pintype "power_in"))
      (node (ref "JP1") (pin "3") (pinfunction "3_3") (pintype "passive"))
      (node (ref "JP1") (pin "4") (pinfunction "4_4") (pintype "passive"))
      (node (ref "JP1") (pin "5") (pinfunction "5_5") (pintype "passive"))
      (node (ref "JP1") (pin "6") (pinfunction "6_6") (pintype "passive"))
      (node (ref "JP1") (pin "7") (pinfunction "7_7") (pintype "passive"))
      (node (ref "JP1") (pin "8") (pinfunction "8_8") (pintype "passive"))
      (node (ref "J_BLUE") (pin "P1") (pinfunction "1_P1") (pintype "passive"))
      (node (ref "J_BLUE") (pin "P2") (pinfunction "2_P2") (pintype "passive"))
      (node (ref "J_GREEN") (pin "P1") (pinfunction "1_P1") (pintype "passive"))
      (node (ref "J_GREEN") (pin "P2") (pinfunction "2_P2") (pintype "passive"))
      (node (ref "J_RED") (pin "P1") (pinfunction "1_P1") (pintype "passive"))
      (node (ref "J_RED") (pin "P2") (pinfunction "2_P2") (pintype "passive"))
      (node (ref "MOD_A") (pin "P1") (pinfunction "1_P1") (pintype "passive"))
      (node (ref "MOD_B") (pin "P1") (pinfunction "1_P1") (pintype "passive"))
      (node (ref "Q1") (pin "E") (pinfunction "E_E") (pintype "passive"))
      (node (ref "Q2") (pin "E") (pinfunction "E_E") (pintype "passive"))
      (node (ref "Q3") (pin "E") (pinfunction "E_E") (pintype "passive"))
      (node (ref "R22") (pin "1") (pinfunction "1_1") (pintype "passive"))
      (node (ref "R23") (pin "1") (pinfunction "1_1") (pintype "passive"))
      (node (ref "R25") (pin "1") (pinfunction "1_1") (pintype "passive"))
      (node (ref "R34") (pin "1") (pinfunction "1_1") (pintype "passive"))
      (node (ref "R48") (pin "2") (pinfunction "2_2") (pintype "passive"))
      (node (ref "SW7") (pin "1") (pinfunction "1_1") (pintype "passive"))
      (node (ref "SW7") (pin "C") (pinfunction "COM_C") (pintype "passive"))
      (node (ref "SW_BLANK") (pin "B1") (pinfunction "P_B1") (pintype "passive"))
      (node (ref "SW_BLANK") (pin "B2") (pinfunction "P1_B2") (pintype "passive"))
      (node (ref "SW_DOWN") (pin "B1") (pinfunction "P_B1") (pintype "passive"))
      (node (ref "SW_DOWN") (pin "B2") (pinfunction "P1_B2") (pintype "passive"))
      (node (ref "SW_LEFT") (pin "B1") (pinfunction "P_B1") (pintype "passive"))
      (node (ref "SW_LEFT") (pin "B2") (pinfunction "P1_B2") (pintype "passive"))
      (node (ref "SW_PLAY") (pin "B1") (pinfunction "P_B1") (pintype "passive"))
      (node (ref "SW_PLAY") (pin "B2") (pinfunction "P1_B2") (pintype "passive"))
      (node (ref "SW_RECORD") (pin "B1") (pinfunction "P_B1") (pintype "passive"))
      (node (ref "SW_RECORD") (pin "B2") (pinfunction "P1_B2") (pintype "passive"))
      (node (ref "SW_RIGHT") (pin "B1") (pinfunction "P_B1") (pintype "passive"))
      (node (ref "SW_RIGHT") (pin "B2") (pinfunction "P1_B2") (pintype "passive"))
      (node (ref "SW_UP") (pin "B1") (pinfunction "P_B1") (pintype "passive"))
      (node (ref "SW_UP") (pin "B2") (pinfunction "P1_B2") (pintype "passive"))
      (node (ref "U$2") (pin "GND1") (pinfunction "GND1_GND1") (pintype "bidirectional"))
      (node (ref "U$2") (pin "GND2") (pinfunction "GND2_GND2") (pintype "bidirectional"))
      (node (ref "U$2") (pin "GND3") (pinfunction "GND3_GND3") (pintype "bidirectional"))
      (node (ref "U$2") (pin "GND4") (pinfunction "GND4_GND4") (pintype "bidirectional"))
      (node (ref "U$2") (pin "GND5") (pinfunction "GND5_GND5") (pintype "bidirectional"))
      (node (ref "U$2") (pin "GND6") (pinfunction "GND6_GND6") (pintype "bidirectional"))
      (node (ref "U$3") (pin "1") (pinfunction "GND_1") (pintype "power_in"))
      (node (ref "VR1") (pin "A1") (pinfunction "CCW_1_A1") (pintype "bidirectional"))
      (node (ref "VR1") (pin "B1") (pinfunction "CCW_2_B1") (pintype "bidirectional"))
      (node (ref "VR1") (pin "MH1") (pinfunction "MH1_MH1") (pintype "bidirectional"))
      (node (ref "VR1") (pin "MH2") (pinfunction "MH2_MH2") (pintype "bidirectional"))
      (node (ref "X1") (pin "18") (pinfunction "18_18") (pintype "passive"))
      (node (ref "X1") (pin "19") (pinfunction "19_19") (pintype "passive"))
      (node (ref "X1") (pin "20") (pinfunction "20_20") (pintype "passive"))
      (node (ref "X1") (pin "25") (pinfunction "25_25") (pintype "passive"))
      (node (ref "X2") (pin "4") (pinfunction "4_4") (pintype "passive"))
      (node (ref "X_IN") (pin "P1") (pinfunction "1_P1") (pintype "passive"))
      (node (ref "Y_IN") (pin "P1") (pinfunction "1_P1") (pintype "passive"))
    )
    (net (code "19") (name "INH1") (class "Default")
      (node (ref "IC9") (pin "6") (pinfunction "INH_6") (pintype "input"))
      (node (ref "U$2") (pin "31-CTX3") (pinfunction "31-CTX3_31-CTX3") (pintype "bidirectional"))
    )
    (net (code "20") (name "INH2") (class "Default")
      (node (ref "IC1") (pin "6") (pinfunction "INH_6") (pintype "input"))
      (node (ref "U$2") (pin "28-RX7") (pinfunction "28-RX7_28-RX7") (pintype "bidirectional"))
    )
    (net (code "21") (name "INTENS{slash}BLANK+") (class "Default")
      (node (ref "X1") (pin "3") (pinfunction "3_3") (pintype "passive"))
    )
    (net (code "22") (name "INTENS{slash}BLANK-") (class "Default")
      (node (ref "X1") (pin "16") (pinfunction "16_16") (pintype "passive"))
    )
    (net (code "23") (name "INTERLOCK") (class "Default")
      (node (ref "JP2") (pin "3") (pinfunction "3_3") (pintype "passive"))
      (node (ref "X1") (pin "4") (pinfunction "4_4") (pintype "passive"))
    )
    (net (code "24") (name "INTERLOCK2") (class "Default")
      (node (ref "JP2") (pin "2") (pinfunction "2_2") (pintype "passive"))
      (node (ref "X1") (pin "17") (pinfunction "17_17") (pintype "passive"))
    )
    (net (code "25") (name "LRCLK") (class "Default")
      (node (ref "IC5") (pin "19") (pinfunction "DAC_LRCK_19") (pintype "bidirectional"))
      (node (ref "IC5") (pin "5") (pinfunction "ADC_LRCK_5") (pintype "bidirectional"))
      (node (ref "U$2") (pin "20-A6/TX5/LRCLK1") (pinfunction "20-A6/TX5/LRCLK1_20-A6/TX5/LRCLK1") (pintype "bidirectional"))
    )
    (net (code "26") (name "MCLK") (class "Default")
      (node (ref "IC5") (pin "10") (pinfunction "MCLK_10") (pintype "bidirectional"))
      (node (ref "U$2") (pin "23-A9/CRX1/MCLK1") (pinfunction "23-A9/CRX1/MCLK1_23-A9/CRX1/MCLK1") (pintype "bidirectional"))
    )
    (net (code "27") (name "MISO") (class "Default")
      (node (ref "U$2") (pin "12-MISO/MQSL") (pinfunction "12-MISO/MQSL_12-MISO/MQSL") (pintype "bidirectional"))
    )
    (net (code "28") (name "MOD_A") (class "Default")
      (node (ref "C14") (pin "2") (pinfunction "2_2") (pintype "passive"))
      (node (ref "IC5") (pin "50") (pinfunction "AIN3+_50") (pintype "bidirectional"))
      (node (ref "IC8") (pin "1") (pinfunction "OUT_1") (pintype "output"))
      (node (ref "R37") (pin "1") (pinfunction "1_1") (pintype "passive"))
      (node (ref "U$2") (pin "14-A0/TX3/SPDIF_OUT") (pinfunction "14-A0/TX3/SPDIF_OUT_14-A0/TX3/SPDIF_OUT") (pintype "bidirectional"))
    )
    (net (code "29") (name "MOD_B") (class "Default")
      (node (ref "C16") (pin "2") (pinfunction "2_2") (pintype "passive"))
      (node (ref "IC5") (pin "52") (pinfunction "AIN4+_52") (pintype "bidirectional"))
      (node (ref "IC8") (pin "7") (pinfunction "OUT_7") (pintype "output"))
      (node (ref "R40") (pin "1") (pinfunction "1_1") (pintype "passive"))
      (node (ref "U$2") (pin "15-A1/RX3/SPDIF_IN") (pinfunction "15-A1/RX3/SPDIF_IN_15-A1/RX3/SPDIF_IN") (pintype "bidirectional"))
    )
    (net (code "30") (name "MOSI") (class "Default")
      (node (ref "U$2") (pin "11-MOSI/CTX1") (pinfunction "11-MOSI/CTX1_11-MOSI/CTX1") (pintype "bidirectional"))
    )
    (net (code "31") (name "MUXA") (class "Default")
      (node (ref "IC1") (pin "11") (pinfunction "A_11") (pintype "input"))
      (node (ref "IC9") (pin "11") (pinfunction "A_11") (pintype "input"))
      (node (ref "U$2") (pin "29-TX7") (pinfunction "29-TX7_29-TX7") (pintype "bidirectional"))
    )
    (net (code "32") (name "MUXB") (class "Default")
      (node (ref "IC1") (pin "10") (pinfunction "B_10") (pintype "input"))
      (node (ref "IC9") (pin "10") (pinfunction "B_10") (pintype "input"))
      (node (ref "U$2") (pin "34-RX8") (pinfunction "34-RX8_34-RX8") (pintype "bidirectional"))
    )
    (net (code "33") (name "MUXC") (class "Default")
      (node (ref "IC1") (pin "9") (pinfunction "C_9") (pintype "input"))
      (node (ref "IC9") (pin "9") (pinfunction "C_9") (pintype "input"))
      (node (ref "U$2") (pin "35-TX8") (pinfunction "35/TX8_35-TX8") (pintype "bidirectional"))
    )
    (net (code "34") (name "MUXOUT1") (class "Default")
      (node (ref "IC9") (pin "3") (pinfunction "X_3") (pintype "bidirectional"))
      (node (ref "U$2") (pin "24-A10/TX6/SCL2") (pinfunction "24-A10/TX6/SCL2_24-A10/TX6/SCL2") (pintype "bidirectional"))
    )
    (net (code "35") (name "MUXOUT2") (class "Default")
      (node (ref "IC1") (pin "3") (pinfunction "X_3") (pintype "bidirectional"))
      (node (ref "U$2") (pin "25-A11/RX6/SDA2") (pinfunction "25-A11/RX6/SDA2_25-A11/RX6/SDA2") (pintype "bidirectional"))
    )
    (net (code "36") (name "Net-(IC1A-X0)") (class "Default")
      (node (ref "IC1") (pin "13") (pinfunction "X0_13") (pintype "bidirectional"))
      (node (ref "R17") (pin "1") (pinfunction "1_1") (pintype "passive"))
      (node (ref "SW7") (pin "2") (pinfunction "2_2") (pintype "passive"))
    )
    (net (code "37") (name "Net-(IC1A-X1)") (class "Default")
      (node (ref "IC1") (pin "14") (pinfunction "X1_14") (pintype "bidirectional"))
      (node (ref "R1") (pin "1") (pinfunction "1_1") (pintype "passive"))
      (node (ref "SW_RECORD") (pin "A1") (pinfunction "S_A1") (pintype "passive"))
      (node (ref "SW_RECORD") (pin "A2") (pinfunction "S1_A2") (pintype "passive"))
    )
    (net (code "38") (name "Net-(IC1A-X2)") (class "Default")
      (node (ref "IC1") (pin "15") (pinfunction "X2_15") (pintype "bidirectional"))
      (node (ref "R2") (pin "1") (pinfunction "1_1") (pintype "passive"))
      (node (ref "SW_BLANK") (pin "A1") (pinfunction "S_A1") (pintype "passive"))
      (node (ref "SW_BLANK") (pin "A2") (pinfunction "S1_A2") (pintype "passive"))
    )
    (net (code "39") (name "Net-(IC1A-X3)") (class "Default")
      (node (ref "IC1") (pin "12") (pinfunction "X3_12") (pintype "bidirectional"))
      (node (ref "R3") (pin "1") (pinfunction "1_1") (pintype "passive"))
      (node (ref "SW_PLAY") (pin "A1") (pinfunction "S_A1") (pintype "passive"))
      (node (ref "SW_PLAY") (pin "A2") (pinfunction "S1_A2") (pintype "passive"))
    )
    (net (code "40") (name "Net-(IC1A-X4)") (class "Default")
      (node (ref "IC1") (pin "1") (pinfunction "X4_1") (pintype "bidirectional"))
      (node (ref "R4") (pin "1") (pinfunction "1_1") (pintype "passive"))
      (node (ref "SW_RIGHT") (pin "A1") (pinfunction "S_A1") (pintype "passive"))
      (node (ref "SW_RIGHT") (pin "A2") (pinfunction "S1_A2") (pintype "passive"))
    )
    (net (code "41") (name "Net-(IC1A-X5)") (class "Default")
      (node (ref "IC1") (pin "5") (pinfunction "X5_5") (pintype "bidirectional"))
      (node (ref "R5") (pin "1") (pinfunction "1_1") (pintype "passive"))
      (node (ref "SW_LEFT") (pin "A1") (pinfunction "S_A1") (pintype "passive"))
      (node (ref "SW_LEFT") (pin "A2") (pinfunction "S1_A2") (pintype "passive"))
    )
    (net (code "42") (name "Net-(IC1A-X6)") (class "Default")
      (node (ref "IC1") (pin "2") (pinfunction "X6_2") (pintype "bidirectional"))
      (node (ref "R6") (pin "1") (pinfunction "1_1") (pintype "passive"))
      (node (ref "SW_DOWN") (pin "A1") (pinfunction "S_A1") (pintype "passive"))
      (node (ref "SW_DOWN") (pin "A2") (pinfunction "S1_A2") (pintype "passive"))
    )
    (net (code "43") (name "Net-(IC1A-X7)") (class "Default")
      (node (ref "IC1") (pin "4") (pinfunction "X7_4") (pintype "bidirectional"))
      (node (ref "R15") (pin "1") (pinfunction "1_1") (pintype "passive"))
      (node (ref "SW_UP") (pin "A1") (pinfunction "S_A1") (pintype "passive"))
      (node (ref "SW_UP") (pin "A2") (pinfunction "S1_A2") (pintype "passive"))
    )
    (net (code "44") (name "Net-(IC2-VIN)") (class "Default")
      (node (ref "C12") (pin "+") (pinfunction "+_+") (pintype "passive"))
      (node (ref "IC2") (pin "2") (pinfunction "VIN_2") (pintype "input"))
      (node (ref "R7") (pin "1") (pinfunction "1_1") (pintype "passive"))
    )
    (net (code "45") (name "Net-(IC4A--IN)") (class "Default")
      (node (ref "IC4") (pin "2") (pinfunction "-IN_2") (pintype "input"))
      (node (ref "R30") (pin "1") (pinfunction "1_1") (pintype "passive"))
      (node (ref "R31") (pin "2") (pinfunction "2_2") (pintype "passive"))
    )
    (net (code "46") (name "Net-(IC4A-OUT)") (class "Default")
      (node (ref "IC4") (pin "1") (pinfunction "OUT_1") (pintype "output"))
      (node (ref "R16") (pin "1") (pinfunction "1_1") (pintype "passive"))
      (node (ref "R30") (pin "2") (pinfunction "2_2") (pintype "passive"))
    )
    (net (code "47") (name "Net-(IC4B--IN)") (class "Default")
      (node (ref "IC4") (pin "6") (pinfunction "-IN_6") (pintype "input"))
      (node (ref "IC4") (pin "7") (pinfunction "OUT_7") (pintype "output"))
      (node (ref "R35") (pin "1") (pinfunction "1_1") (pintype "passive"))
    )
    (net (code "48") (name "Net-(IC4C--IN)") (class "Default")
      (node (ref "IC4") (pin "9") (pinfunction "-IN_9") (pintype "input"))
      (node (ref "R32") (pin "1") (pinfunction "1_1") (pintype "passive"))
      (node (ref "R33") (pin "2") (pinfunction "2_2") (pintype "passive"))
    )
    (net (code "49") (name "Net-(IC4C-OUT)") (class "Default")
      (node (ref "IC4") (pin "8") (pinfunction "OUT_8") (pintype "output"))
      (node (ref "R24") (pin "1") (pinfunction "1_1") (pintype "passive"))
      (node (ref "R32") (pin "2") (pinfunction "2_2") (pintype "passive"))
    )
    (net (code "50") (name "Net-(IC4D--IN)") (class "Default")
      (node (ref "IC4") (pin "13") (pinfunction "-IN_13") (pintype "input"))
      (node (ref "IC4") (pin "14") (pinfunction "OUT_14") (pintype "output"))
      (node (ref "R21") (pin "1") (pinfunction "1_1") (pintype "passive"))
    )
    (net (code "51") (name "Net-(IC5-AD0{slash}~{CS})") (class "Default")
      (node (ref "IC5") (pin "1") (pinfunction "AD0/~{CS}_1") (pintype "bidirectional"))
      (node (ref "R34") (pin "2") (pinfunction "2_2") (pintype "passive"))
    )
    (net (code "52") (name "Net-(IC5-AIN1-)") (class "Default")
      (node (ref "C19") (pin "1") (pinfunction "1_1") (pintype "passive"))
      (node (ref "IC5") (pin "45") (pinfunction "AIN1-_45") (pintype "bidirectional"))
    )
    (net (code "53") (name "Net-(IC5-AIN2-)") (class "Default")
      (node (ref "C22") (pin "1") (pinfunction "1_1") (pintype "passive"))
      (node (ref "IC5") (pin "47") (pinfunction "AIN2-_47") (pintype "bidirectional"))
    )
    (net (code "54") (name "Net-(IC5-AIN3-)") (class "Default")
      (node (ref "C23") (pin "1") (pinfunction "1_1") (pintype "passive"))
      (node (ref "IC5") (pin "49") (pinfunction "AIN3-_49") (pintype "bidirectional"))
    )
    (net (code "55") (name "Net-(IC5-AIN4-)") (class "Default")
      (node (ref "C24") (pin "1") (pinfunction "1_1") (pintype "passive"))
      (node (ref "IC5") (pin "51") (pinfunction "AIN4-_51") (pintype "bidirectional"))
    )
    (net (code "56") (name "Net-(IC5-FILT+_ADC)") (class "Default")
      (node (ref "C26") (pin "1") (pinfunction "1_1") (pintype "passive"))
      (node (ref "C27") (pin "1") (pinfunction "1_1") (pintype "passive"))
      (node (ref "IC5") (pin "55") (pinfunction "FILT+_ADC_55") (pintype "bidirectional"))
    )
    (net (code "57") (name "Net-(IC5-FILT+_DAC)") (class "Default")
      (node (ref "C25") (pin "1") (pinfunction "1_1") (pintype "passive"))
      (node (ref "C28") (pin "1") (pinfunction "1_1") (pintype "passive"))
      (node (ref "IC5") (pin "54") (pinfunction "FILT+_DAC_54") (pintype "bidirectional"))
    )
    (net (code "58") (name "Net-(IC5-VQ)") (class "Default")
      (node (ref "C20") (pin "1") (pinfunction "1_1") (pintype "passive"))
      (node (ref "C29") (pin "1") (pinfunction "1_1") (pintype "passive"))
      (node (ref "IC5") (pin "43") (pinfunction "VQ_43") (pintype "bidirectional"))
      (node (ref "TEST_VQ") (pin "P$1") (pinfunction "1_P$1") (pintype "bidirectional"))
    )
    (net (code "59") (name "Net-(IC5-~{RST})") (class "Default")
      (node (ref "IC5") (pin "3") (pinfunction "~{RST}_3") (pintype "bidirectional"))
      (node (ref "IC7") (pin "2") (pinfunction "~{RESET}_2") (pintype "bidirectional"))
    )
    (net (code "60") (name "Net-(IC6A--IN)") (class "Default")
      (node (ref "C15") (pin "1") (pinfunction "1_1") (pintype "passive"))
      (node (ref "IC6") (pin "2") (pinfunction "-IN_2") (pintype "input"))
      (node (ref "R10") (pin "1") (pinfunction "1_1") (pintype "passive"))
      (node (ref "R8") (pin "1") (pinfunction "1_1") (pintype "passive"))
      (node (ref "R9") (pin "2") (pinfunction "2_2") (pintype "passive"))
    )
    (net (code "61") (name "Net-(IC6B--IN)") (class "Default")
      (node (ref "C13") (pin "1") (pinfunction "1_1") (pintype "passive"))
      (node (ref "IC6") (pin "6") (pinfunction "-IN_6") (pintype "input"))
      (node (ref "R11") (pin "1") (pinfunction "1_1") (pintype "passive"))
      (node (ref "R13") (pin "2") (pinfunction "2_2") (pintype "passive"))
      (node (ref "R14") (pin "1") (pinfunction "1_1") (pintype "passive"))
    )
    (net (code "62") (name "Net-(IC8A--IN)") (class "Default")
      (node (ref "C14") (pin "1") (pinfunction "1_1") (pintype "passive"))
      (node (ref "IC8") (pin "2") (pinfunction "-IN_2") (pintype "input"))
      (node (ref "R36") (pin "1") (pinfunction "1_1") (pintype "passive"))
      (node (ref "R37") (pin "2") (pinfunction "2_2") (pintype "passive"))
      (node (ref "R38") (pin "1") (pinfunction "1_1") (pintype "passive"))
    )
    (net (code "63") (name "Net-(IC8B--IN)") (class "Default")
      (node (ref "C16") (pin "1") (pinfunction "1_1") (pintype "passive"))
      (node (ref "IC8") (pin "6") (pinfunction "-IN_6") (pintype "input"))
      (node (ref "R39") (pin "1") (pinfunction "1_1") (pintype "passive"))
      (node (ref "R40") (pin "2") (pinfunction "2_2") (pintype "passive"))
      (node (ref "R41") (pin "1") (pinfunction "1_1") (pintype "passive"))
    )
    (net (code "64") (name "Net-(IC9A-X0)") (class "Default")
      (node (ref "IC9") (pin "13") (pinfunction "X0_13") (pintype "bidirectional"))
      (node (ref "P_RED") (pin "P$2") (pinfunction "S_P$2") (pintype "passive"))
    )
    (net (code "65") (name "Net-(IC9A-X1)") (class "Default")
      (node (ref "IC9") (pin "14") (pinfunction "X1_14") (pintype "bidirectional"))
      (node (ref "P_BLUE") (pin "P$2") (pinfunction "S_P$2") (pintype "passive"))
    )
    (net (code "66") (name "Net-(IC9A-X2)") (class "Default")
      (node (ref "IC9") (pin "15") (pinfunction "X2_15") (pintype "bidirectional"))
      (node (ref "P_GREEN") (pin "P$2") (pinfunction "S_P$2") (pintype "passive"))
    )
    (net (code "67") (name "Net-(IC9A-X3)") (class "Default")
      (node (ref "IC9") (pin "12") (pinfunction "X3_12") (pintype "bidirectional"))
      (node (ref "P_X") (pin "P$2") (pinfunction "S_P$2") (pintype "passive"))
    )
    (net (code "68") (name "Net-(IC9A-X4)") (class "Default")
      (node (ref "IC9") (pin "1") (pinfunction "X4_1") (pintype "bidirectional"))
      (node (ref "P_Y") (pin "P$2") (pinfunction "S_P$2") (pintype "passive"))
    )
    (net (code "69") (name "Net-(IC9A-X5)") (class "Default")
      (node (ref "IC9") (pin "5") (pinfunction "X5_5") (pintype "bidirectional"))
      (node (ref "P_MODA") (pin "P$2") (pinfunction "S_P$2") (pintype "passive"))
    )
    (net (code "70") (name "Net-(IC9A-X6)") (class "Default")
      (node (ref "IC9") (pin "2") (pinfunction "X6_2") (pintype "bidirectional"))
      (node (ref "P_MODB") (pin "P$2") (pinfunction "S_P$2") (pintype "passive"))
    )
    (net (code "71") (name "Net-(IC9A-X7)") (class "Default")
      (node (ref "IC9") (pin "4") (pinfunction "X7_4") (pintype "bidirectional"))
      (node (ref "P_SAMPLE") (pin "P$2") (pinfunction "S_P$2") (pintype "passive"))
    )
    (net (code "72") (name "Net-(IC10C--IN)") (class "Default")
      (node (ref "IC10") (pin "8") (pinfunction "OUT_8") (pintype "output"))
      (node (ref "IC10") (pin "9") (pinfunction "-IN_9") (pintype "input"))
      (node (ref "R18") (pin "1") (pinfunction "1_1") (pintype "passive"))
    )
    (net (code "73") (name "Net-(JP1-Pad1)") (class "Default")
      (node (ref "JP1") (pin "1") (pinfunction "1_1") (pintype "passive"))
      (node (ref "JP1") (pin "2") (pinfunction "2_2") (pintype "passive"))
      (node (ref "P2") (pin "2") (pinfunction "2_2") (pintype "bidirectional"))
    )
    (net (code "74") (name "Net-(JP1-Pad10)") (class "Default")
      (node (ref "JP1") (pin "10") (pinfunction "10_10") (pintype "passive"))
      (node (ref "JP1") (pin "9") (pinfunction "9_9") (pintype "passive"))
      (node (ref "P1") (pin "2") (pinfunction "2_2") (pintype "bidirectional"))
    )
    (net (code "75") (name "Net-(JP1-Pad11)") (class "Default")
      (node (ref "JP1") (pin "11") (pinfunction "11_11") (pintype "passive"))
      (node (ref "JP1") (pin "12") (pinfunction "12_12") (pintype "passive"))
      (node (ref "P3") (pin "2") (pinfunction "2_2") (pintype "bidirectional"))
    )
    (net (code "76") (name "Net-(J_BLUE-3)") (class "Default")
      (node (ref "J_BLUE") (pin "P3") (pinfunction "3_P3") (pintype "passive"))
      (node (ref "R46") (pin "1") (pinfunction "1_1") (pintype "passive"))
    )
    (net (code "77") (name "Net-(J_GREEN-3)") (class "Default")
      (node (ref "J_GREEN") (pin "P3") (pinfunction "3_P3") (pintype "passive"))
      (node (ref "R44") (pin "1") (pinfunction "1_1") (pintype "passive"))
    )
    (net (code "78") (name "Net-(J_RED-3)") (class "Default")
      (node (ref "J_RED") (pin "P3") (pinfunction "3_P3") (pintype "passive"))
      (node (ref "R42") (pin "1") (pinfunction "1_1") (pintype "passive"))
    )
    (net (code "79") (name "Net-(MOD_A-3)") (class "Default")
      (node (ref "MOD_A") (pin "P3") (pinfunction "3_P3") (pintype "passive"))
      (node (ref "R36") (pin "2") (pinfunction "2_2") (pintype "passive"))
    )
    (net (code "80") (name "Net-(MOD_B-3)") (class "Default")
      (node (ref "MOD_B") (pin "P3") (pinfunction "3_P3") (pintype "passive"))
      (node (ref "R39") (pin "2") (pinfunction "2_2") (pintype "passive"))
    )
    (net (code "81") (name "Net-(Q1-PadB)") (class "Default")
      (node (ref "Q1") (pin "B") (pinfunction "B_B") (pintype "passive"))
      (node (ref "R44") (pin "2") (pinfunction "2_2") (pintype "passive"))
    )
    (net (code "82") (name "Net-(Q2-PadB)") (class "Default")
      (node (ref "Q2") (pin "B") (pinfunction "B_B") (pintype "passive"))
      (node (ref "R42") (pin "2") (pinfunction "2_2") (pintype "passive"))
    )
    (net (code "83") (name "Net-(Q3-PadB)") (class "Default")
      (node (ref "Q3") (pin "B") (pinfunction "B_B") (pintype "passive"))
      (node (ref "R46") (pin "2") (pinfunction "2_2") (pintype "passive"))
    )
    (net (code "84") (name "Net-(R26-Pad1)") (class "Default")
      (node (ref "R26") (pin "1") (pinfunction "1_1") (pintype "passive"))
      (node (ref "R28") (pin "1") (pinfunction "1_1") (pintype "passive"))
      (node (ref "TM1") (pin "S") (pinfunction "S_S") (pintype "passive"))
    )
    (net (code "85") (name "Net-(U$2-5V)") (class "Default")
      (node (ref "U$2") (pin "+5V") (pinfunction "5V_+5V") (pintype "bidirectional"))
      (node (ref "X2") (pin "1") (pinfunction "1_1") (pintype "passive"))
    )
    (net (code "86") (name "Net-(U$2-PadDM)") (class "Default")
      (node (ref "U$2") (pin "DM") (pinfunction "DM_DM") (pintype "bidirectional"))
      (node (ref "X2") (pin "2") (pinfunction "2_2") (pintype "passive"))
    )
    (net (code "87") (name "Net-(U$2-PadDP)") (class "Default")
      (node (ref "U$2") (pin "DP") (pinfunction "DP_DP") (pintype "bidirectional"))
      (node (ref "X2") (pin "3") (pinfunction "3_3") (pintype "passive"))
    )
    (net (code "88") (name "Net-(U1A--IN)") (class "Default")
      (node (ref "R26") (pin "2") (pinfunction "2_2") (pintype "passive"))
      (node (ref "R27") (pin "1") (pinfunction "1_1") (pintype "passive"))
      (node (ref "U1") (pin "2") (pinfunction "-IN_2") (pintype "input"))
    )
    (net (code "89") (name "Net-(U1B--IN)") (class "Default")
      (node (ref "R28") (pin "2") (pinfunction "2_2") (pintype "passive"))
      (node (ref "R29") (pin "1") (pinfunction "1_1") (pintype "passive"))
      (node (ref "U1") (pin "6") (pinfunction "-IN_6") (pintype "input"))
    )
    (net (code "90") (name "Net-(VR1-CW_1)") (class "Default")
      (node (ref "R11") (pin "2") (pinfunction "2_2") (pintype "passive"))
      (node (ref "VR1") (pin "A3") (pinfunction "CW_1_A3") (pintype "bidirectional"))
    )
    (net (code "91") (name "Net-(VR1-CW_2)") (class "Default")
      (node (ref "R8") (pin "2") (pinfunction "2_2") (pintype "passive"))
      (node (ref "VR1") (pin "B3") (pinfunction "CW_2_B3") (pintype "bidirectional"))
    )
    (net (code "92") (name "Net-(VR1-WIPER_1)") (class "Default")
      (node (ref "VR1") (pin "A2") (pinfunction "WIPER_1_A2") (pintype "bidirectional"))
      (node (ref "Y_IN") (pin "P3") (pinfunction "3_P3") (pintype "passive"))
    )
    (net (code "93") (name "Net-(VR1-WIPER_2)") (class "Default")
      (node (ref "VR1") (pin "B2") (pinfunction "WIPER_2_B2") (pintype "bidirectional"))
      (node (ref "X_IN") (pin "P3") (pinfunction "3_P3") (pintype "passive"))
    )
    (net (code "94") (name "Net-(X_AUDIO-3)") (class "Default")
      (node (ref "R49") (pin "2") (pinfunction "2_2") (pintype "passive"))
      (node (ref "X_AUDIO") (pin "P3") (pinfunction "3_P3") (pintype "passive"))
    )
    (net (code "95") (name "Net-(Y_AUDIO-3)") (class "Default")
      (node (ref "R50") (pin "2") (pinfunction "2_2") (pintype "passive"))
      (node (ref "Y_AUDIO") (pin "P3") (pinfunction "3_P3") (pintype "passive"))
    )
    (net (code "96") (name "OUTX") (class "Default")
      (node (ref "IC5") (pin "26") (pinfunction "AOUT1+_26") (pintype "bidirectional"))
      (node (ref "U1") (pin "3") (pinfunction "+IN_3") (pintype "input"))
    )
    (net (code "97") (name "OUTY") (class "Default")
      (node (ref "IC5") (pin "27") (pinfunction "AOUT2+_27") (pintype "bidirectional"))
      (node (ref "U1") (pin "5") (pinfunction "+IN_5") (pintype "input"))
    )
    (net (code "98") (name "R+") (class "Default")
      (node (ref "R20") (pin "2") (pinfunction "2_2") (pintype "passive"))
      (node (ref "X1") (pin "5") (pinfunction "5_5") (pintype "passive"))
    )
    (net (code "99") (name "R1+") (class "Default")
      (node (ref "IC10") (pin "1") (pinfunction "OUT_1") (pintype "output"))
      (node (ref "IC10") (pin "2") (pinfunction "-IN_2") (pintype "input"))
      (node (ref "R20") (pin "1") (pinfunction "1_1") (pintype "passive"))
    )
    (net (code "100") (name "RX_DOUT") (class "Default")
      (node (ref "U$2") (pin "8-TX2/IN1") (pinfunction "8-TX2/IN1_8-TX2/IN1") (pintype "bidirectional"))
    )
    (net (code "101") (name "SCK") (class "Default")
      (node (ref "U$2") (pin "13-SCK/LED") (pinfunction "13-SCK/LED_13-SCK/LED") (pintype "bidirectional"))
    )
    (net (code "102") (name "SCL") (class "Default")
      (node (ref "IC5") (pin "63") (pinfunction "SCL/CCLK_63") (pintype "bidirectional"))
      (node (ref "R52") (pin "1") (pinfunction "1_1") (pintype "passive"))
      (node (ref "U$2") (pin "19-A5/SCL0") (pinfunction "19-A5/SCL0_19-A5/SCL0") (pintype "bidirectional"))
      (node (ref "U$3") (pin "3") (pinfunction "SCL_3") (pintype "bidirectional"))
    )
    (net (code "103") (name "SDA") (class "Default")
      (node (ref "IC5") (pin "64") (pinfunction "SDA/CDOUT_64") (pintype "bidirectional"))
      (node (ref "R51") (pin "1") (pinfunction "1_1") (pintype "passive"))
      (node (ref "U$2") (pin "18-A4/SDA0") (pinfunction "18-A4/SDA0_18-A4/SDA0") (pintype "bidirectional"))
      (node (ref "U$3") (pin "4") (pinfunction "SDA_4") (pintype "bidirectional"))
    )
    (net (code "104") (name "SHUTTER") (class "Default")
      (node (ref "U$2") (pin "30-CRX3") (pinfunction "30-CRX3_30-CRX3") (pintype "bidirectional"))
      (node (ref "X1") (pin "13") (pinfunction "13_13") (pintype "passive"))
    )
    (net (code "105") (name "SS") (class "Default")
      (node (ref "U$2") (pin "10-CS\\MQSR") (pinfunction "10-CS/MQSR_10-CS\\MQSR") (pintype "bidirectional"))
    )
    (net (code "106") (name "T26") (class "Default")
      (node (ref "Q2") (pin "C") (pinfunction "C_C") (pintype "passive"))
      (node (ref "R43") (pin "1") (pinfunction "1_1") (pintype "passive"))
      (node (ref "U$2") (pin "26-A12/MOSI1") (pinfunction "26-A12/MOSI1_26-A12/MOSI1") (pintype "bidirectional"))
    )
    (net (code "107") (name "T27") (class "Default")
      (node (ref "Q1") (pin "C") (pinfunction "C_C") (pintype "passive"))
      (node (ref "R45") (pin "1") (pinfunction "1_1") (pintype "passive"))
      (node (ref "U$2") (pin "27-A13/SCK1") (pinfunction "27-A13/SCK1_27-A13/SCK1") (pintype "bidirectional"))
    )
    (net (code "108") (name "T38") (class "Default")
      (node (ref "Q3") (pin "C") (pinfunction "C_C") (pintype "passive"))
      (node (ref "R47") (pin "1") (pinfunction "1_1") (pintype "passive"))
      (node (ref "U$2") (pin "38-A14/CS/IN1") (pinfunction "38-A14/CS/IN1_38-A14/CS/IN1") (pintype "bidirectional"))
    )
    (net (code "109") (name "T39") (class "Default")
      (node (ref "U$2") (pin "39-A15/CS/OUT1A") (pinfunction "39-A15/CS/OUT1A_39-A15/CS/OUT1A") (pintype "bidirectional"))
    )
    (net (code "110") (name "TB") (class "Default")
      (node (ref "IC10") (pin "10") (pinfunction "+IN_10") (pintype "input"))
      (node (ref "R22") (pin "2") (pinfunction "2_2") (pintype "passive"))
      (node (ref "U$2") (pin "2-OUT2") (pinfunction "2-OUT2_2-OUT2") (pintype "bidirectional"))
    )
    (net (code "111") (name "TDM_IN") (class "Default")
      (node (ref "IC5") (pin "13") (pinfunction "ADC_SDOUT1_13") (pintype "bidirectional"))
    )
    (net (code "112") (name "TDM_OUT") (class "Default")
      (node (ref "IC5") (pin "17") (pinfunction "DAC_SDIN1_17") (pintype "bidirectional"))
    )
    (net (code "113") (name "TG") (class "Default")
      (node (ref "IC10") (pin "5") (pinfunction "+IN_5") (pintype "input"))
      (node (ref "R23") (pin "2") (pinfunction "2_2") (pintype "passive"))
      (node (ref "U$2") (pin "9-OUT1C") (pinfunction "9-OUT1C_9-OUT1C") (pintype "bidirectional"))
    )
    (net (code "114") (name "TR") (class "Default")
      (node (ref "IC10") (pin "3") (pinfunction "+IN_3") (pintype "input"))
      (node (ref "R25") (pin "2") (pinfunction "2_2") (pintype "passive"))
      (node (ref "U$2") (pin "33-MCLK2") (pinfunction "33-MCLK2_33-MCLK2") (pintype "bidirectional"))
    )
    (net (code "115") (name "TX_DIN") (class "Default")
      (node (ref "U$2") (pin "7-RX2/OUT1A") (pinfunction "7-RX2/OUT1A_7-RX2/OUT1A") (pintype "bidirectional"))
    )
    (net (code "116") (name "VCC") (class "Default")
      (node (ref "IC7") (pin "4") (pinfunction "VCC_4") (pintype "power_in"))
    )
    (net (code "117") (name "X+") (class "Default")
      (node (ref "R35") (pin "2") (pinfunction "2_2") (pintype "passive"))
      (node (ref "X1") (pin "1") (pinfunction "1_1") (pintype "passive"))
    )
    (net (code "118") (name "X-") (class "Default")
      (node (ref "R24") (pin "2") (pinfunction "2_2") (pintype "passive"))
      (node (ref "X1") (pin "14") (pinfunction "14_14") (pintype "passive"))
    )
    (net (code "119") (name "X2") (class "Default")
      (node (ref "IC4") (pin "5") (pinfunction "+IN_5") (pintype "input"))
      (node (ref "R27") (pin "2") (pinfunction "2_2") (pintype "passive"))
      (node (ref "R33") (pin "1") (pinfunction "1_1") (pintype "passive"))
      (node (ref "R49") (pin "1") (pinfunction "1_1") (pintype "passive"))
      (node (ref "U1") (pin "1") (pinfunction "OUT_1") (pintype "output"))
    )
    (net (code "120") (name "X_IN") (class "Default")
      (node (ref "C15") (pin "2") (pinfunction "2_2") (pintype "passive"))
      (node (ref "IC5") (pin "46") (pinfunction "AIN1+_46") (pintype "bidirectional"))
      (node (ref "IC6") (pin "1") (pinfunction "OUT_1") (pintype "output"))
      (node (ref "R9") (pin "1") (pinfunction "1_1") (pintype "passive"))
    )
    (net (code "121") (name "Y+") (class "Default")
      (node (ref "R21") (pin "2") (pinfunction "2_2") (pintype "passive"))
      (node (ref "X1") (pin "2") (pinfunction "2_2") (pintype "passive"))
    )
    (net (code "122") (name "Y-") (class "Default")
      (node (ref "R16") (pin "2") (pinfunction "2_2") (pintype "passive"))
      (node (ref "X1") (pin "15") (pinfunction "15_15") (pintype "passive"))
    )
    (net (code "123") (name "Y2") (class "Default")
      (node (ref "IC4") (pin "12") (pinfunction "+IN_12") (pintype "input"))
      (node (ref "R29") (pin "2") (pinfunction "2_2") (pintype "passive"))
      (node (ref "R31") (pin "1") (pinfunction "1_1") (pintype "passive"))
      (node (ref "R50") (pin "1") (pinfunction "1_1") (pintype "passive"))
      (node (ref "U1") (pin "7") (pinfunction "OUT_7") (pintype "output"))
    )
    (net (code "124") (name "Y_IN") (class "Default")
      (node (ref "C13") (pin "2") (pinfunction "2_2") (pintype "passive"))
      (node (ref "IC5") (pin "48") (pinfunction "AIN2+_48") (pintype "bidirectional"))
      (node (ref "IC6") (pin "7") (pinfunction "OUT_7") (pintype "output"))
      (node (ref "R13") (pin "1") (pinfunction "1_1") (pintype "passive"))
    )
    (net (code "125") (name "unconnected-(IC5-ADC_SDOUT2-Pad12)") (class "Default")
      (node (ref "IC5") (pin "12") (pinfunction "ADC_SDOUT2_12") (pintype "bidirectional"))
    )
    (net (code "126") (name "unconnected-(IC5-ADC_SDOUT3-Pad11)") (class "Default")
      (node (ref "IC5") (pin "11") (pinfunction "ADC_SDOUT3_11") (pintype "bidirectional"))
    )
    (net (code "127") (name "unconnected-(IC5-AIN5+{slash}AIN5A-Pad58)") (class "Default")
      (node (ref "IC5") (pin "58") (pinfunction "AIN5+/AIN5A_58") (pintype "bidirectional"))
    )
    (net (code "128") (name "unconnected-(IC5-AIN5-{slash}AIN5B-Pad57)") (class "Default")
      (node (ref "IC5") (pin "57") (pinfunction "AIN5-/AIN5B_57") (pintype "bidirectional"))
    )
    (net (code "129") (name "unconnected-(IC5-AIN6-{slash}AIN6B-Pad59)") (class "Default")
      (node (ref "IC5") (pin "59") (pinfunction "AIN6-/AIN6B_59") (pintype "bidirectional"))
    )
    (net (code "130") (name "unconnected-(IC5-AOUT1--Pad25)") (class "Default")
      (node (ref "IC5") (pin "25") (pinfunction "AOUT1-_25") (pintype "bidirectional"))
    )
    (net (code "131") (name "unconnected-(IC5-AOUT2--Pad28)") (class "Default")
      (node (ref "IC5") (pin "28") (pinfunction "AOUT2-_28") (pintype "bidirectional"))
    )
    (net (code "132") (name "unconnected-(IC5-AOUT3+-Pad30)") (class "Default")
      (node (ref "IC5") (pin "30") (pinfunction "AOUT3+_30") (pintype "bidirectional"))
    )
    (net (code "133") (name "unconnected-(IC5-AOUT3--Pad29)") (class "Default")
      (node (ref "IC5") (pin "29") (pinfunction "AOUT3-_29") (pintype "bidirectional"))
    )
    (net (code "134") (name "unconnected-(IC5-AOUT4+-Pad31)") (class "Default")
      (node (ref "IC5") (pin "31") (pinfunction "AOUT4+_31") (pintype "bidirectional"))
    )
    (net (code "135") (name "unconnected-(IC5-AOUT4--Pad32)") (class "Default")
      (node (ref "IC5") (pin "32") (pinfunction "AOUT4-_32") (pintype "bidirectional"))
    )
    (net (code "136") (name "unconnected-(IC5-AOUT5+-Pad34)") (class "Default")
      (node (ref "IC5") (pin "34") (pinfunction "AOUT5+_34") (pintype "bidirectional"))
    )
    (net (code "137") (name "unconnected-(IC5-AOUT5--Pad33)") (class "Default")
      (node (ref "IC5") (pin "33") (pinfunction "AOUT5-_33") (pintype "bidirectional"))
    )
    (net (code "138") (name "unconnected-(IC5-AOUT6+-Pad36)") (class "Default")
      (node (ref "IC5") (pin "36") (pinfunction "AOUT6+_36") (pintype "bidirectional"))
    )
    (net (code "139") (name "unconnected-(IC5-AOUT6--Pad37)") (class "Default")
      (node (ref "IC5") (pin "37") (pinfunction "AOUT6-_37") (pintype "bidirectional"))
    )
    (net (code "140") (name "unconnected-(IC5-AOUT7+-Pad39)") (class "Default")
      (node (ref "IC5") (pin "39") (pinfunction "AOUT7+_39") (pintype "bidirectional"))
    )
    (net (code "141") (name "unconnected-(IC5-AOUT7--Pad38)") (class "Default")
      (node (ref "IC5") (pin "38") (pinfunction "AOUT7-_38") (pintype "bidirectional"))
    )
    (net (code "142") (name "unconnected-(IC5-AOUT8+-Pad40)") (class "Default")
      (node (ref "IC5") (pin "40") (pinfunction "AOUT8+_40") (pintype "bidirectional"))
    )
    (net (code "143") (name "unconnected-(IC5-AOUT8--Pad41)") (class "Default")
      (node (ref "IC5") (pin "41") (pinfunction "AOUT8-_41") (pintype "bidirectional"))
    )
    (net (code "144") (name "unconnected-(IC5-AUX_LRCK-Pad20)") (class "Default")
      (node (ref "IC5") (pin "20") (pinfunction "AUX_LRCK_20") (pintype "bidirectional"))
    )
    (net (code "145") (name "unconnected-(IC5-AUX_SCLK-Pad21)") (class "Default")
      (node (ref "IC5") (pin "21") (pinfunction "AUX_SCLK_21") (pintype "bidirectional"))
    )
    (net (code "146") (name "unconnected-(IC5-IN6+{slash}AIN6A-Pad60)") (class "Default")
      (node (ref "IC5") (pin "60") (pinfunction "IN6+/AIN6A_60") (pintype "bidirectional"))
    )
    (net (code "147") (name "unconnected-(IC5-INT-Pad61)") (class "Default")
      (node (ref "IC5") (pin "61") (pinfunction "INT_61") (pintype "bidirectional"))
    )
    (net (code "148") (name "unconnected-(IC5-MUTEC-Pad35)") (class "Default")
      (node (ref "IC5") (pin "35") (pinfunction "MUTEC_35") (pintype "bidirectional"))
    )
    (net (code "149") (name "unconnected-(IC7-~{MR}-Pad3)") (class "Default")
      (node (ref "IC7") (pin "3") (pinfunction "~{MR}_3") (pintype "bidirectional"))
    )
    (net (code "150") (name "unconnected-(J1-Pad1)") (class "Default")
      (node (ref "J1") (pin "1") (pinfunction "1_1") (pintype "passive"))
    )
    (net (code "151") (name "unconnected-(J1-Pad2)") (class "Default")
      (node (ref "J1") (pin "2") (pinfunction "2_2") (pintype "passive"))
    )
    (net (code "152") (name "unconnected-(J1-Pad3)") (class "Default")
      (node (ref "J1") (pin "3") (pinfunction "3_3") (pintype "passive"))
    )
    (net (code "153") (name "unconnected-(J1-Pad4)") (class "Default")
      (node (ref "J1") (pin "4") (pinfunction "4_4") (pintype "passive"))
    )
    (net (code "154") (name "unconnected-(J1-Pad5)") (class "Default")
      (node (ref "J1") (pin "5") (pinfunction "5_5") (pintype "passive"))
    )
    (net (code "155") (name "unconnected-(J1-Pad6)") (class "Default")
      (node (ref "J1") (pin "6") (pinfunction "6_6") (pintype "passive"))
    )
    (net (code "156") (name "unconnected-(J1-Pad7)") (class "Default")
      (node (ref "J1") (pin "7") (pinfunction "7_7") (pintype "passive"))
    )
    (net (code "157") (name "unconnected-(J1-Pad8)") (class "Default")
      (node (ref "J1") (pin "8") (pinfunction "8_8") (pintype "passive"))
    )
    (net (code "158") (name "unconnected-(J1-Pad9)") (class "Default")
      (node (ref "J1") (pin "9") (pinfunction "9_9") (pintype "passive"))
    )
    (net (code "159") (name "unconnected-(J1-Pad10)") (class "Default")
      (node (ref "J1") (pin "10") (pinfunction "10_10") (pintype "passive"))
    )
    (net (code "160") (name "unconnected-(J1-Pad11)") (class "Default")
      (node (ref "J1") (pin "11") (pinfunction "11_11") (pintype "passive"))
    )
    (net (code "161") (name "unconnected-(J1-Pad12)") (class "Default")
      (node (ref "J1") (pin "12") (pinfunction "12_12") (pintype "passive"))
    )
    (net (code "162") (name "unconnected-(J1-Pad13)") (class "Default")
      (node (ref "J1") (pin "13") (pinfunction "13_13") (pintype "passive"))
    )
    (net (code "163") (name "unconnected-(J1-Pad14)") (class "Default")
      (node (ref "J1") (pin "14") (pinfunction "14_14") (pintype "passive"))
    )
    (net (code "164") (name "unconnected-(J1-Pad15)") (class "Default")
      (node (ref "J1") (pin "15") (pinfunction "15_15") (pintype "passive"))
    )
    (net (code "165") (name "unconnected-(J1-Pad16)") (class "Default")
      (node (ref "J1") (pin "16") (pinfunction "16_16") (pintype "passive"))
    )
    (net (code "166") (name "unconnected-(J1-Pad17)") (class "Default")
      (node (ref "J1") (pin "17") (pinfunction "17_17") (pintype "passive"))
    )
    (net (code "167") (name "unconnected-(J1-Pad18)") (class "Default")
      (node (ref "J1") (pin "18") (pinfunction "18_18") (pintype "passive"))
    )
    (net (code "168") (name "unconnected-(J1-Pad19)") (class "Default")
      (node (ref "J1") (pin "19") (pinfunction "19_19") (pintype "passive"))
    )
    (net (code "169") (name "unconnected-(J1-Pad20)") (class "Default")
      (node (ref "J1") (pin "20") (pinfunction "20_20") (pintype "passive"))
    )
    (net (code "170") (name "unconnected-(J1-Pad21)") (class "Default")
      (node (ref "J1") (pin "21") (pinfunction "21_21") (pintype "passive"))
    )
    (net (code "171") (name "unconnected-(J1-Pad22)") (class "Default")
      (node (ref "J1") (pin "22") (pinfunction "22_22") (pintype "passive"))
    )
    (net (code "172") (name "unconnected-(J1-Pad23)") (class "Default")
      (node (ref "J1") (pin "23") (pinfunction "23_23") (pintype "passive"))
    )
    (net (code "173") (name "unconnected-(J1-Pad24)") (class "Default")
      (node (ref "J1") (pin "24") (pinfunction "24_24") (pintype "passive"))
    )
    (net (code "174") (name "unconnected-(J1-Pad25)") (class "Default")
      (node (ref "J1") (pin "25") (pinfunction "25_25") (pintype "passive"))
    )
    (net (code "175") (name "unconnected-(J1-Pad26)") (class "Default")
      (node (ref "J1") (pin "26") (pinfunction "26_26") (pintype "passive"))
    )
    (net (code "176") (name "unconnected-(JP1-Pad13)") (class "Default")
      (node (ref "JP1") (pin "13") (pinfunction "13_13") (pintype "passive"))
    )
    (net (code "177") (name "unconnected-(JP1-Pad14)") (class "Default")
      (node (ref "JP1") (pin "14") (pinfunction "14_14") (pintype "passive"))
    )
    (net (code "178") (name "unconnected-(JP1-Pad15)") (class "Default")
      (node (ref "JP1") (pin "15") (pinfunction "15_15") (pintype "passive"))
    )
    (net (code "179") (name "unconnected-(JP1-Pad16)") (class "Default")
      (node (ref "JP1") (pin "16") (pinfunction "16_16") (pintype "passive"))
    )
    (net (code "180") (name "unconnected-(JP2-Pad1)") (class "Default")
      (node (ref "JP2") (pin "1") (pinfunction "1_1") (pintype "passive"))
    )
    (net (code "181") (name "unconnected-(U$2-Pad0-RX1{slash}CS1{slash}CRX2)") (class "Default")
      (node (ref "U$2") (pin "0-RX1/CS1/CRX2") (pinfunction "0-RX1/CS1/CRX2_0-RX1/CS1/CRX2") (pintype "bidirectional"))
    )
    (net (code "182") (name "unconnected-(U$2-Pad1-TX1{slash}MISO1{slash}CTX2)") (class "Default")
      (node (ref "U$2") (pin "1-TX1/MISO1/CTX2") (pinfunction "1-TX1/MISO1/CTX2_1-TX1/MISO1/CTX2") (pintype "bidirectional"))
    )
    (net (code "183") (name "unconnected-(U$2-Pad3-LRCLK2)") (class "Default")
      (node (ref "U$2") (pin "3-LRCLK2") (pinfunction "3-LRCLK2_3-LRCLK2") (pintype "bidirectional"))
    )
    (net (code "184") (name "unconnected-(U$2-Pad3V3-2)") (class "Default")
      (node (ref "U$2") (pin "3V3-2") (pinfunction "3V3-2_3V3-2") (pintype "bidirectional"))
    )
    (net (code "185") (name "unconnected-(U$2-Pad3V3-3)") (class "Default")
      (node (ref "U$2") (pin "3V3-3") (pinfunction "3V3-3_3V3-3") (pintype "bidirectional"))
    )
    (net (code "186") (name "unconnected-(U$2-Pad4-BCLK2)") (class "Default")
      (node (ref "U$2") (pin "4-BCLK2") (pinfunction "4-BCLK2_4-BCLK2") (pintype "bidirectional"))
    )
    (net (code "187") (name "unconnected-(U$2-Pad5-IN2)") (class "Default")
      (node (ref "U$2") (pin "5-IN2") (pinfunction "5-IN2_5-IN2") (pintype "bidirectional"))
    )
    (net (code "188") (name "unconnected-(U$2-Pad6-OUT1D)") (class "Default")
      (node (ref "U$2") (pin "6-OUT1D") (pinfunction "6-OUT1D_6-OUT1D") (pintype "bidirectional"))
    )
    (net (code "189") (name "unconnected-(U$2-Pad16-A2{slash}RX4{slash}SCL1)") (class "Default")
      (node (ref "U$2") (pin "16-A2/RX4/SCL1") (pinfunction "16-A2/RX4/SCL1_16-A2/RX4/SCL1") (pintype "bidirectional"))
    )
    (net (code "190") (name "unconnected-(U$2-Pad17-A3{slash}TX4{slash}SDA1)") (class "Default")
      (node (ref "U$2") (pin "17-A3/TX4/SDA1") (pinfunction "17-A3/TX4/SDA1_17-A3/TX4/SDA1") (pintype "bidirectional"))
    )
    (net (code "191") (name "unconnected-(U$2-Pad32-OUT1B)") (class "Default")
      (node (ref "U$2") (pin "32-OUT1B") (pinfunction "32-OUT1B_32-OUT1B") (pintype "bidirectional"))
    )
    (net (code "192") (name "unconnected-(U$2-Pad36-PWM)") (class "Default")
      (node (ref "U$2") (pin "36-PWM") (pinfunction "36-PWM_36-PWM") (pintype "bidirectional"))
    )
    (net (code "193") (name "unconnected-(U$2-Pad37-PWM)") (class "Default")
      (node (ref "U$2") (pin "37-PWM") (pinfunction "37-PWM_37-PWM") (pintype "bidirectional"))
    )
    (net (code "194") (name "unconnected-(U$2-PadON{slash}OFF)") (class "Default")
      (node (ref "U$2") (pin "ON/OFF") (pinfunction "ON/OFF_ON/OFF") (pintype "bidirectional"))
    )
    (net (code "195") (name "unconnected-(U$2-PadPROGRAM)") (class "Default")
      (node (ref "U$2") (pin "PROGRAM") (pinfunction "PROGRAM_PROGRAM") (pintype "bidirectional"))
    )
    (net (code "196") (name "unconnected-(U$2-PadVBAT)") (class "Default")
      (node (ref "U$2") (pin "VBAT") (pinfunction "VBAT_VBAT") (pintype "bidirectional"))
    )
    (net (code "197") (name "unconnected-(U$2-PadVUSB)") (class "Default")
      (node (ref "U$2") (pin "VUSB") (pinfunction "VUSB_VUSB") (pintype "bidirectional"))
    )
    (net (code "198") (name "unconnected-(X1-Pad8)") (class "Default")
      (node (ref "X1") (pin "8") (pinfunction "8_8") (pintype "passive"))
    )
    (net (code "199") (name "unconnected-(X1-Pad9)") (class "Default")
      (node (ref "X1") (pin "9") (pinfunction "9_9") (pintype "passive"))
    )
    (net (code "200") (name "unconnected-(X1-Pad10)") (class "Default")
      (node (ref "X1") (pin "10") (pinfunction "10_10") (pintype "passive"))
    )
    (net (code "201") (name "unconnected-(X1-Pad11)") (class "Default")
      (node (ref "X1") (pin "11") (pinfunction "11_11") (pintype "passive"))
    )
    (net (code "202") (name "unconnected-(X1-Pad12)") (class "Default")
      (node (ref "X1") (pin "12") (pinfunction "12_12") (pintype "passive"))
    )
    (net (code "203") (name "unconnected-(X1-Pad21)") (class "Default")
      (node (ref "X1") (pin "21") (pinfunction "21_21") (pintype "passive"))
    )
    (net (code "204") (name "unconnected-(X1-Pad22)") (class "Default")
      (node (ref "X1") (pin "22") (pinfunction "22_22") (pintype "passive"))
    )
    (net (code "205") (name "unconnected-(X1-Pad23)") (class "Default")
      (node (ref "X1") (pin "23") (pinfunction "23_23") (pintype "passive"))
    )
    (net (code "206") (name "unconnected-(X1-Pad24)") (class "Default")
      (node (ref "X1") (pin "24") (pinfunction "24_24") (pintype "passive"))
    )
    (net (code "207") (name "unconnected-(X_AUDIO-2-PadP2)") (class "Default")
      (node (ref "X_AUDIO") (pin "P2") (pinfunction "2_P2") (pintype "passive"))
    )
    (net (code "208") (name "unconnected-(Y_AUDIO-2-PadP2)") (class "Default")
      (node (ref "Y_AUDIO") (pin "P2") (pinfunction "2_P2") (pintype "passive"))
    )
    (net (code "209") (name "~{LDAC}") (class "Default")
      (node (ref "U$2") (pin "22-A8/CTX1") (pinfunction "22-A8/CTX1_22-A8/CTX1") (pintype "bidirectional"))
    )
  )
)
